# Motherboard.net
KiCad netlist of a schematic drawn in EAGLE
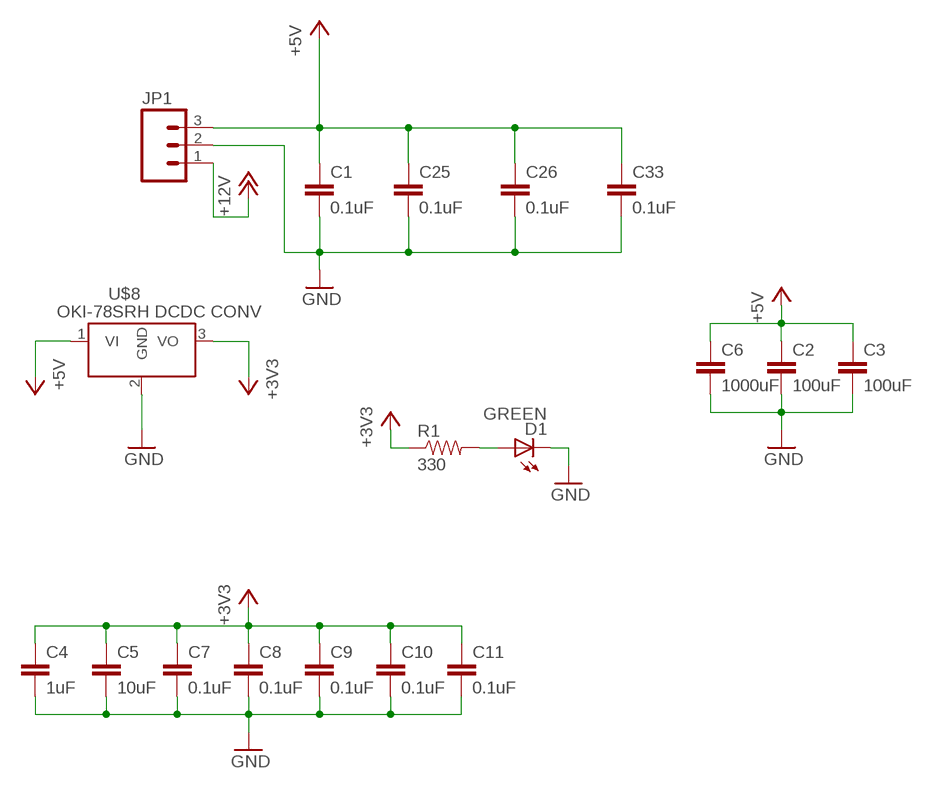
[diagram p0: schematic, sheet 1]
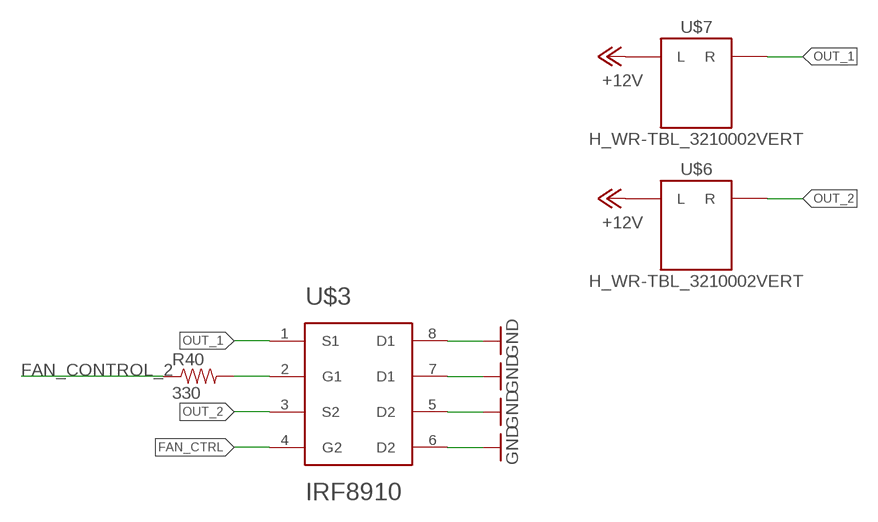
[diagram p1: schematic, sheet 2]
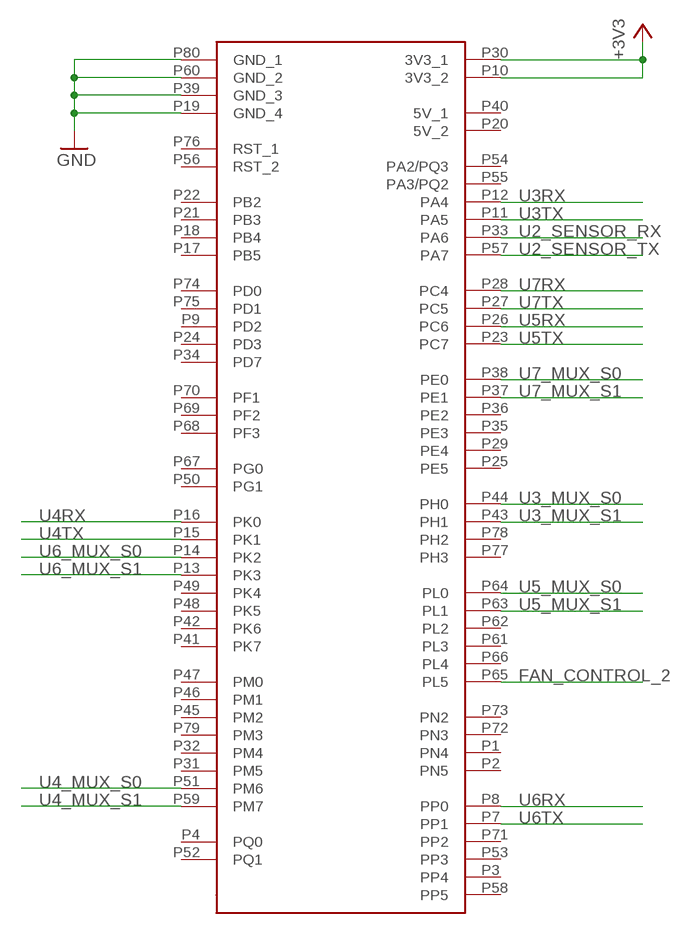
[diagram p2: schematic, sheet 3]
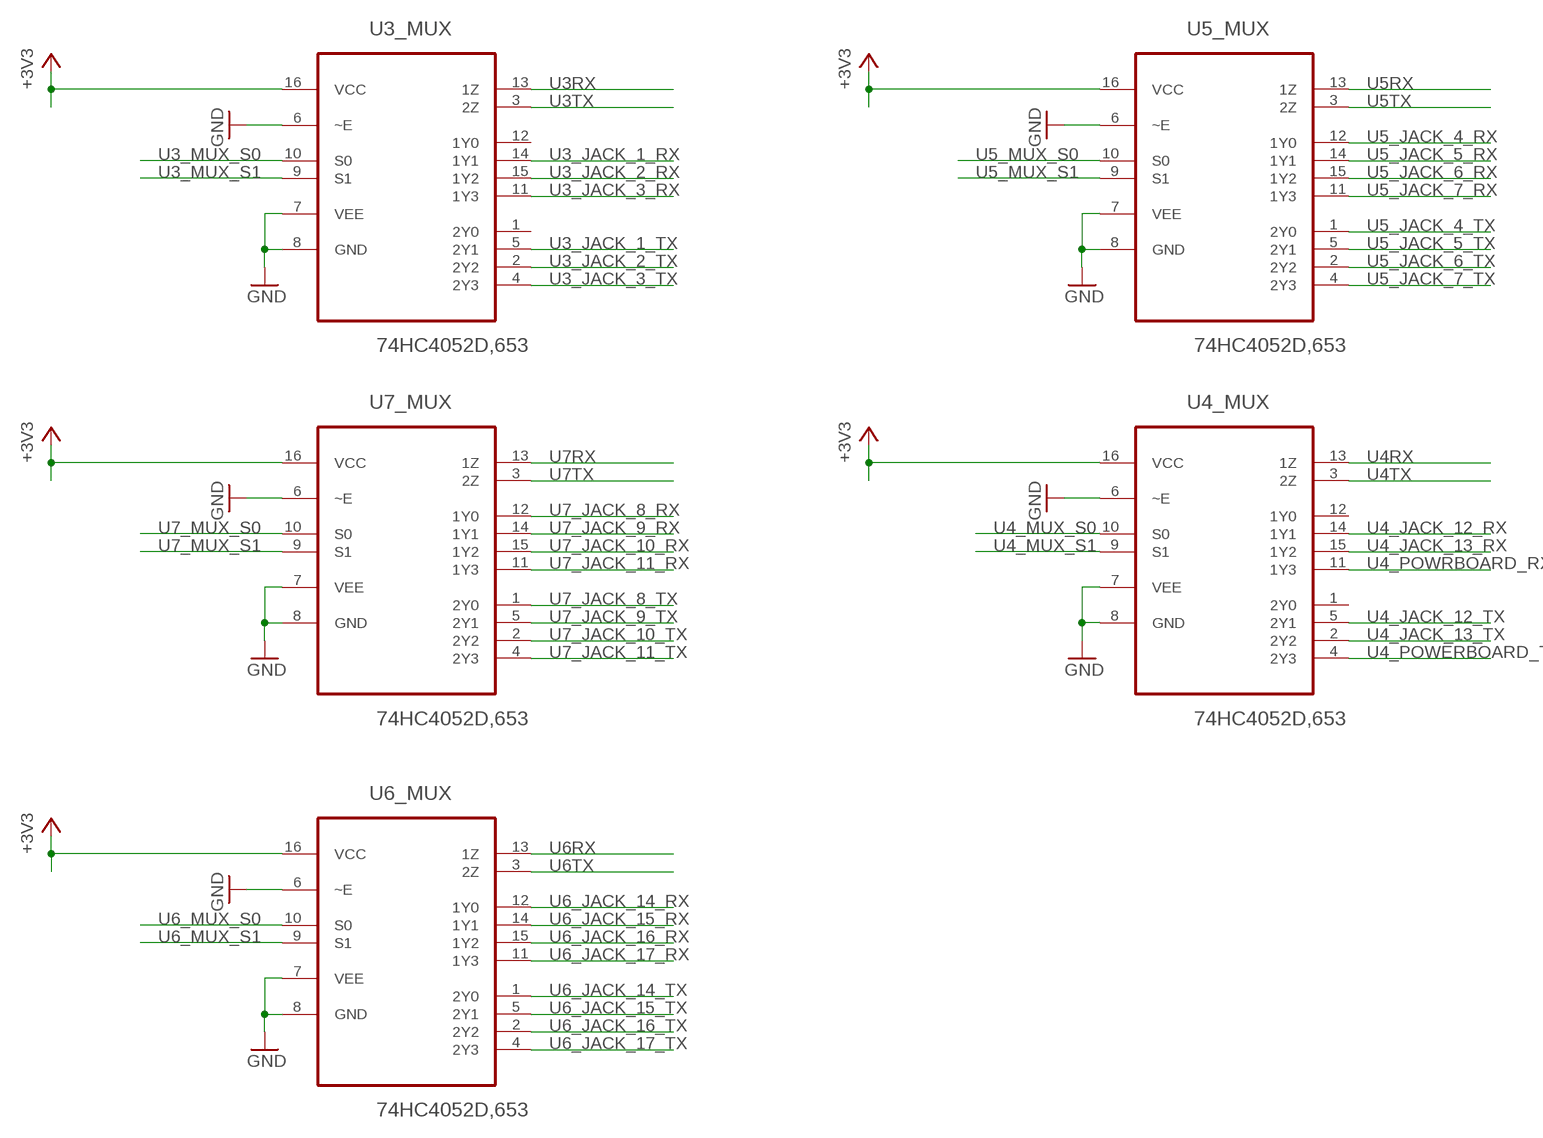
[diagram p3: schematic, sheet 4]
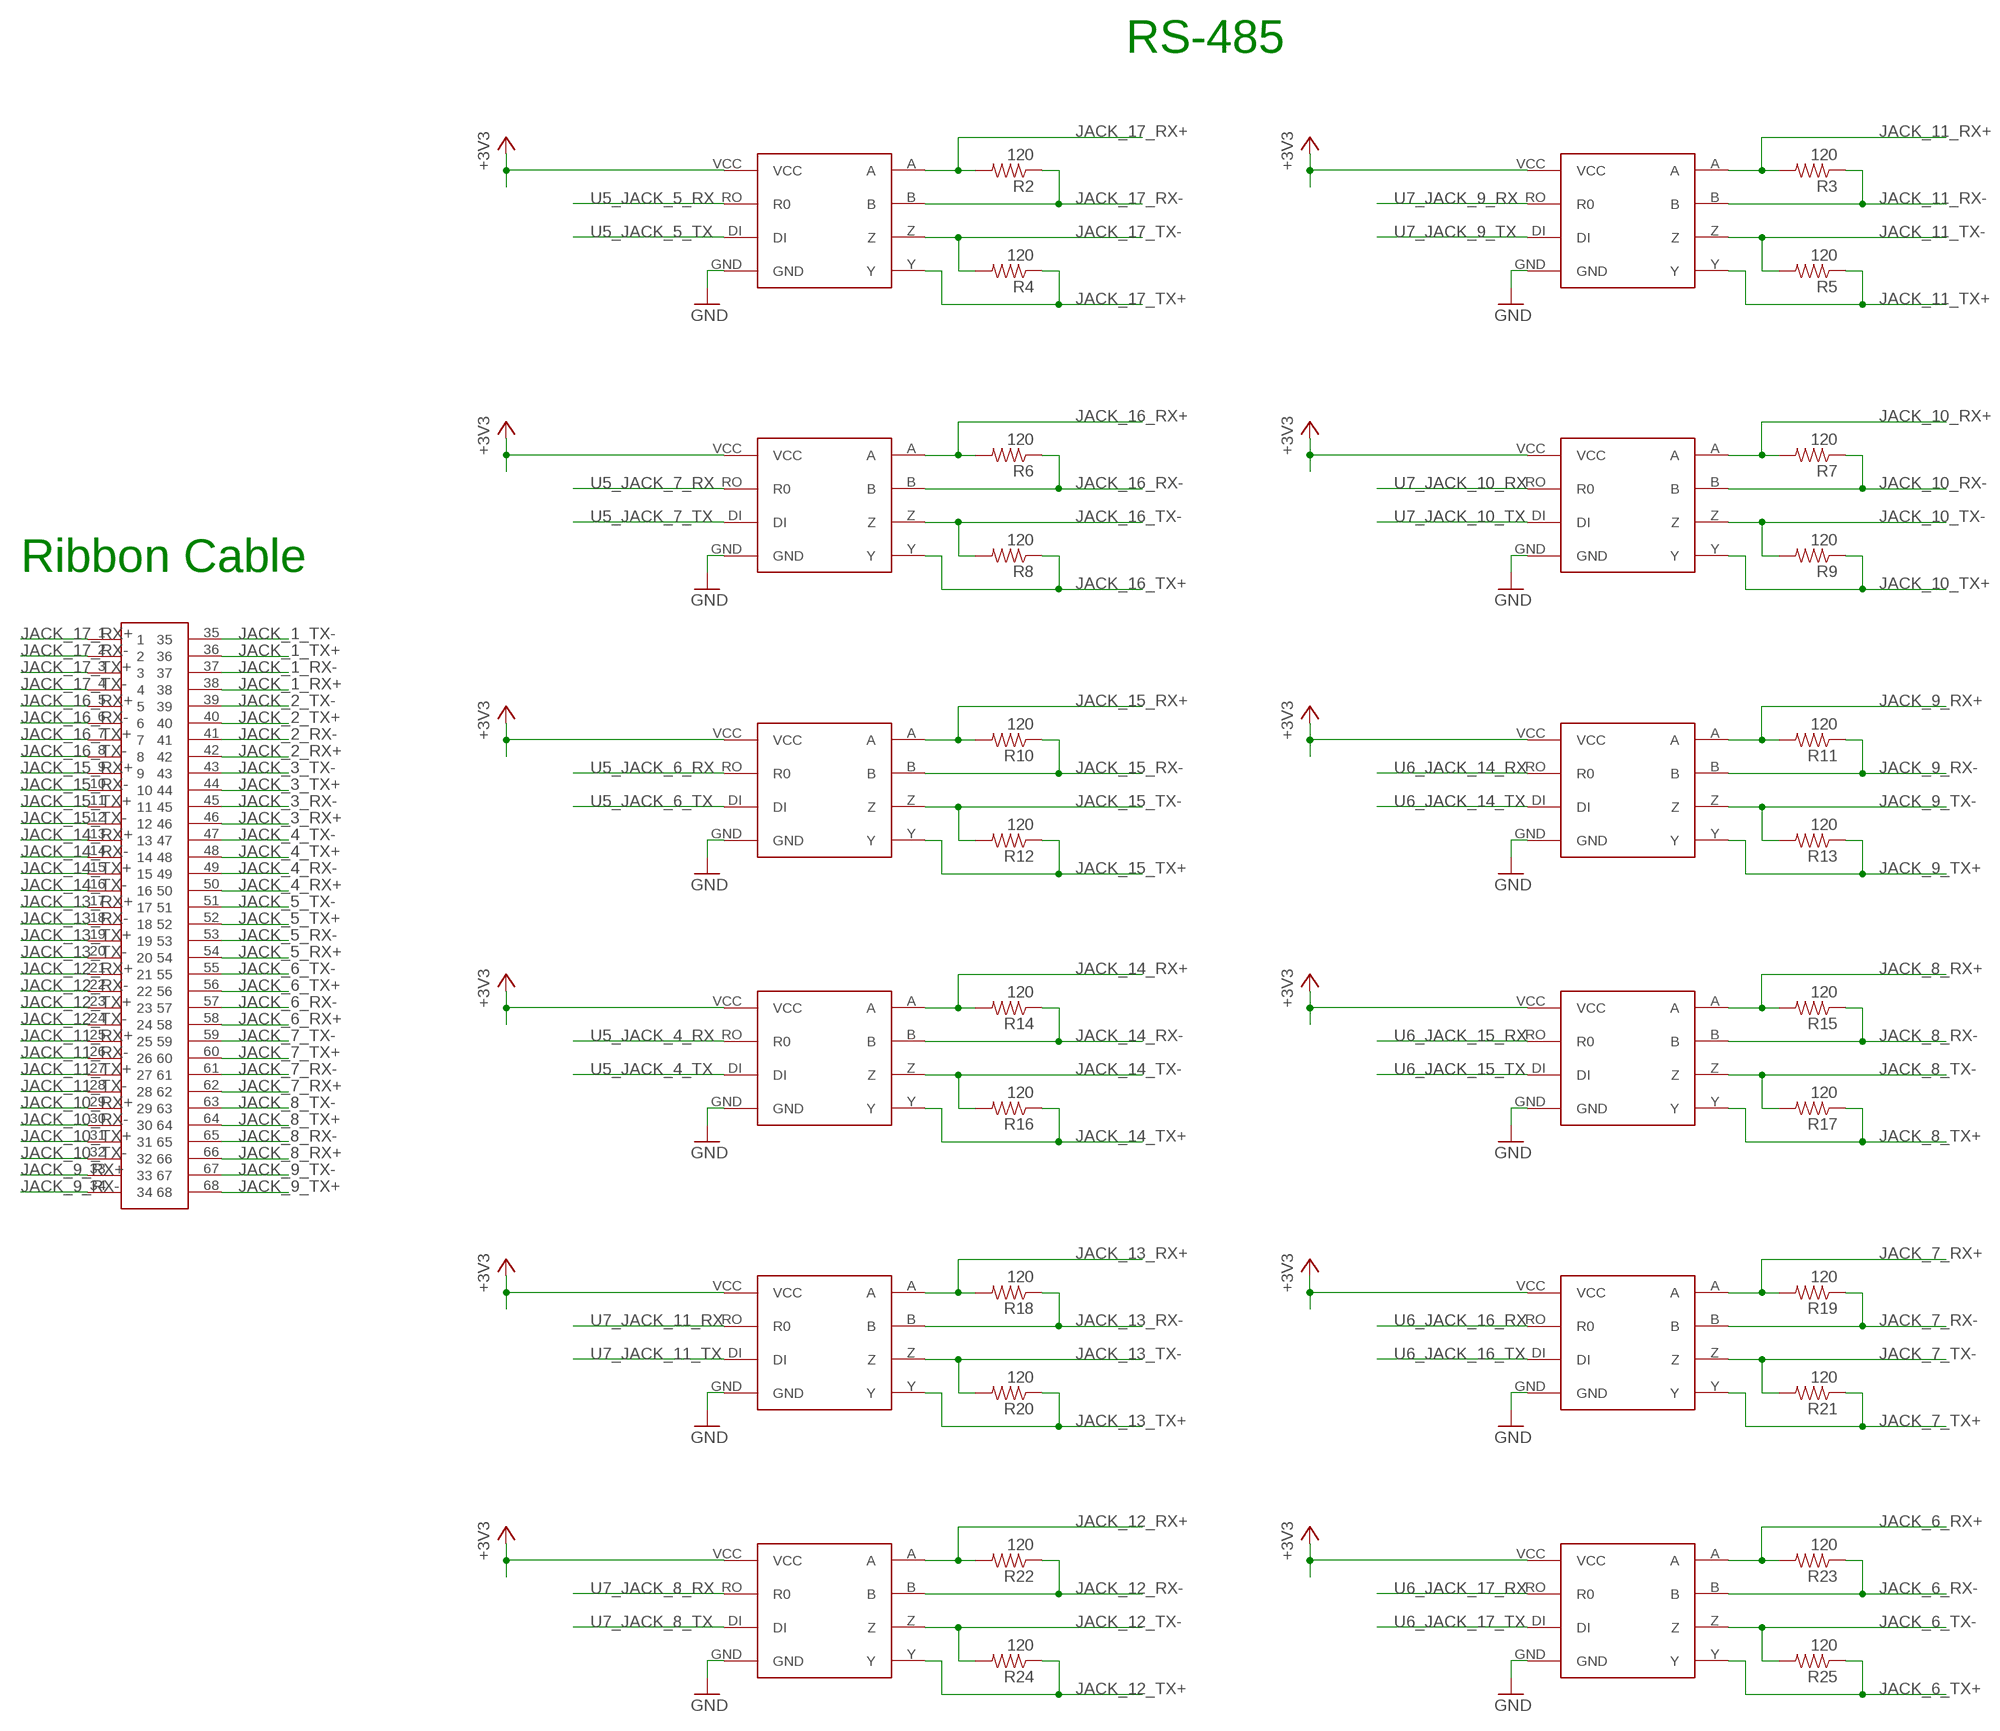
[diagram p4: schematic, sheet 5, part 1 of 2]
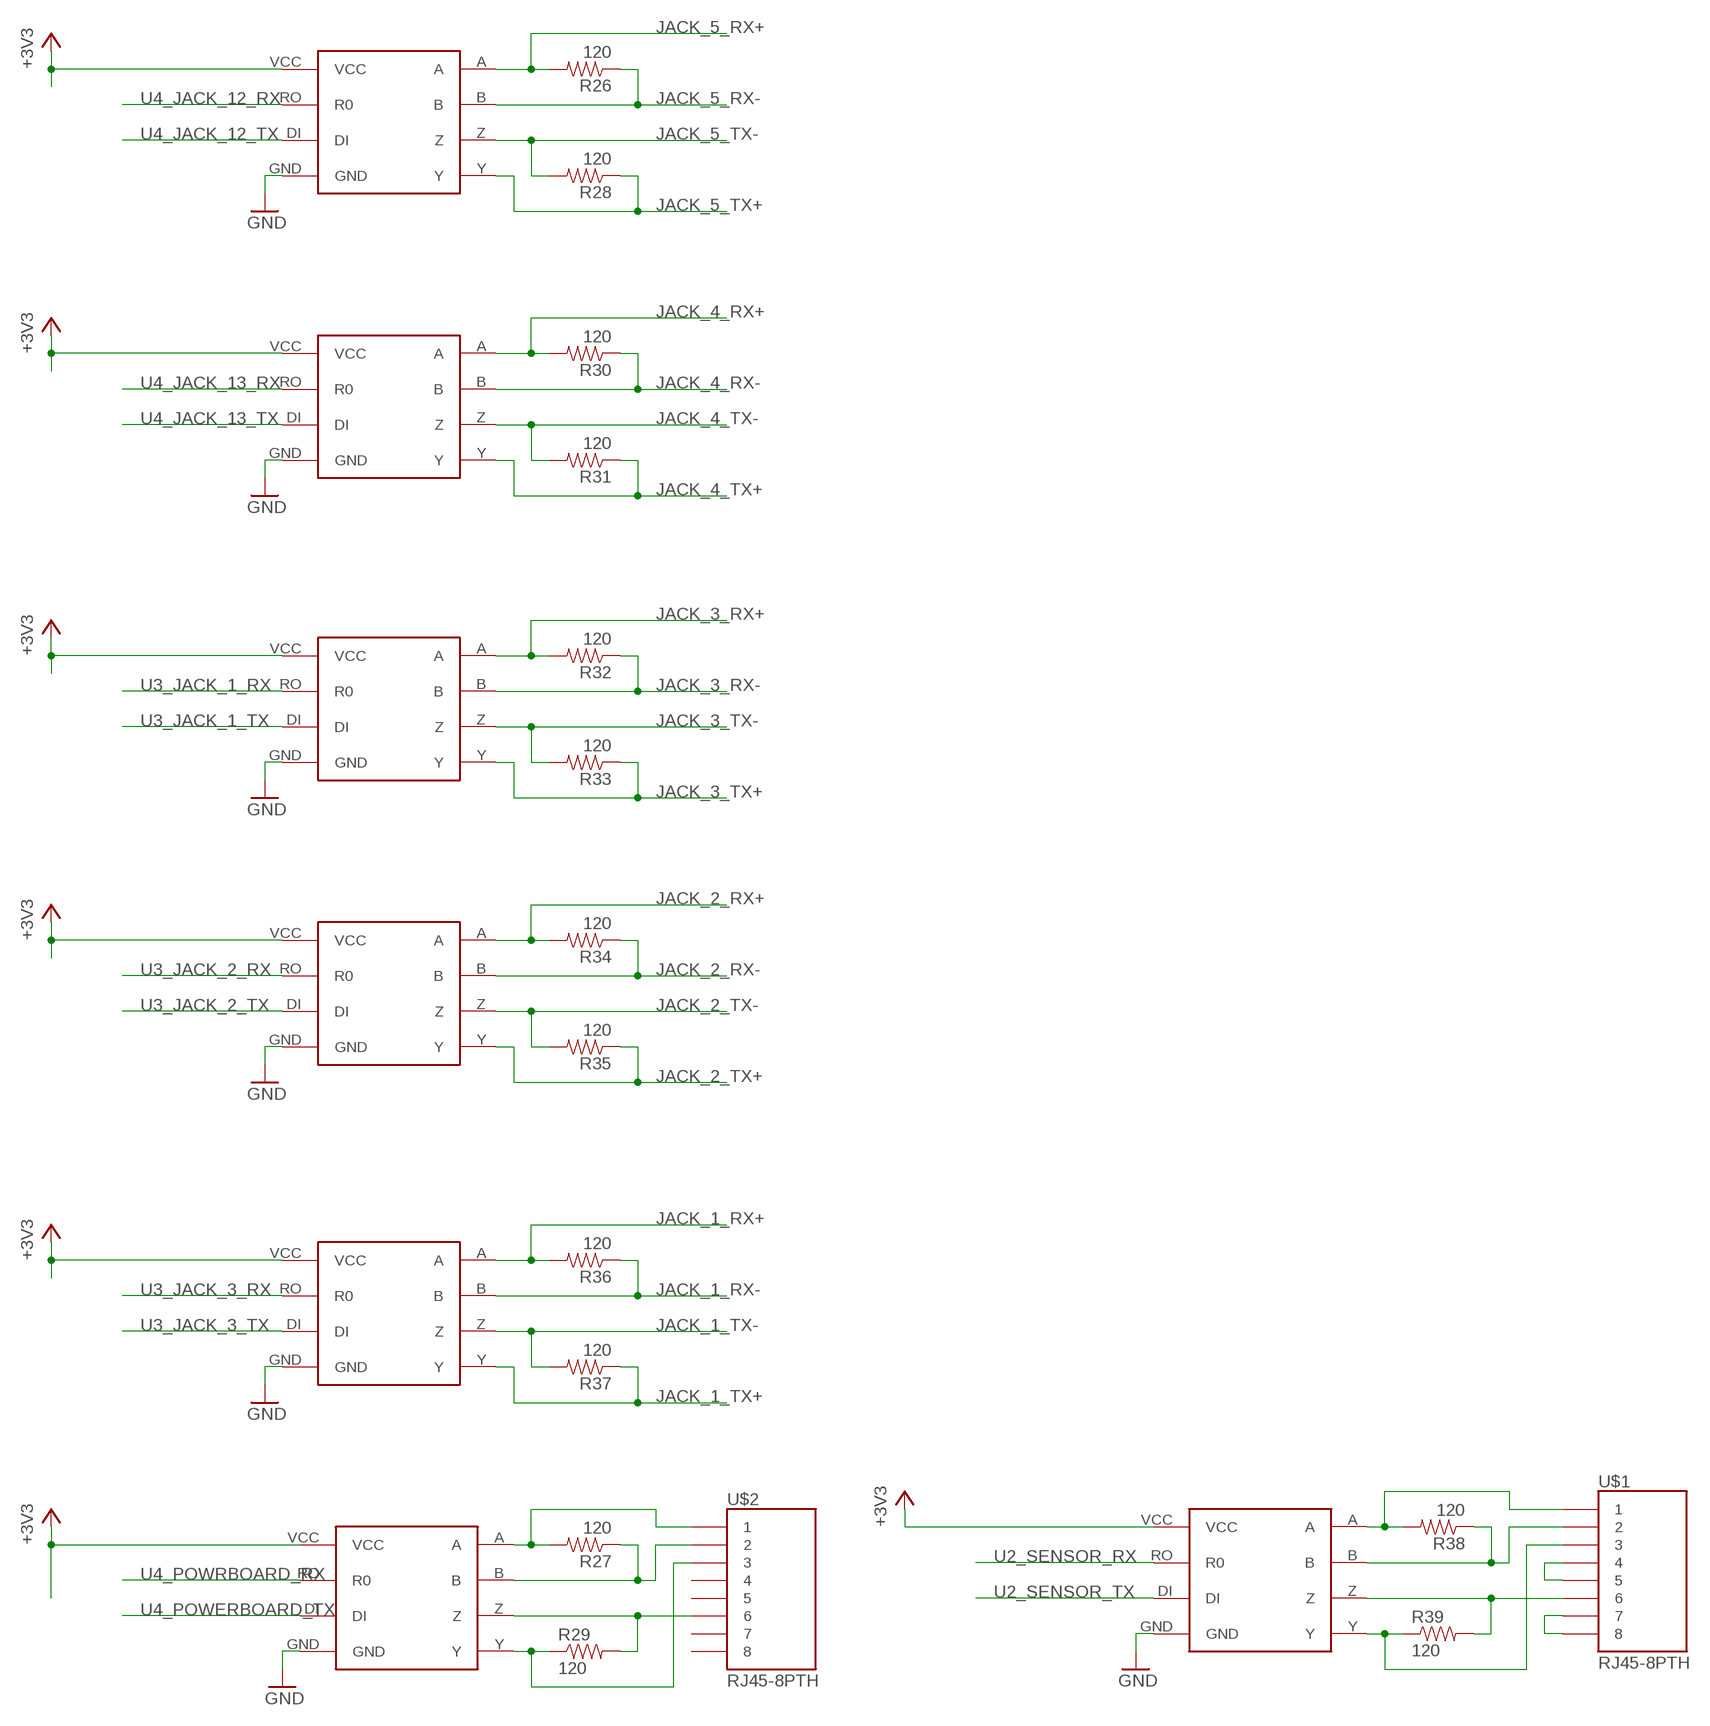
[diagram p5: schematic, sheet 5, part 2 of 2]
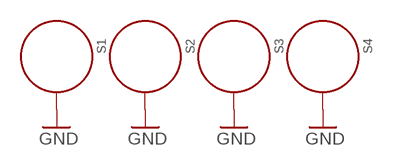
[diagram p6: schematic, sheet 6]

(export (version "E")
  (design (tool "Eeschema 10.0.6"))
  (components
    (comp (ref "S1")
      (value "STANDOFF_ELECTRICAL")
      (footprint "eagle-import:STANDOFF-ELECTRICAL")
      (libsource (lib "eagle-import") (part "STANDOFF_ELECTRICAL"))
    )
    (comp (ref "S2")
      (value "STANDOFF_ELECTRICAL")
      (footprint "eagle-import:STANDOFF-ELECTRICAL")
      (libsource (lib "eagle-import") (part "STANDOFF_ELECTRICAL"))
    )
    (comp (ref "S3")
      (value "STANDOFF_ELECTRICAL")
      (footprint "eagle-import:STANDOFF-ELECTRICAL")
      (libsource (lib "eagle-import") (part "STANDOFF_ELECTRICAL"))
    )
    (comp (ref "S4")
      (value "STANDOFF_ELECTRICAL")
      (footprint "eagle-import:STANDOFF-ELECTRICAL")
      (libsource (lib "eagle-import") (part "STANDOFF_ELECTRICAL"))
    )
    (comp (ref "R40")
      (value "330")
      (footprint "eagle-import:1206")
      (libsource (lib "eagle-import") (part "RESISTOR1206"))
    )
    (comp (ref "U$3")
      (value "IRF8910")
      (footprint "eagle-import:SO8")
      (libsource (lib "eagle-import") (part "IRF8910"))
    )
    (comp (ref "U$6")
      (value "H_WR-TBL_3210002VERT")
      (footprint "eagle-import:691321100002")
      (libsource (lib "eagle-import") (part "H_WR-TBL_3210002VERT"))
    )
    (comp (ref "U$7")
      (value "H_WR-TBL_3210002VERT")
      (footprint "eagle-import:691321100002")
      (libsource (lib "eagle-import") (part "H_WR-TBL_3210002VERT"))
    )
    (comp (ref "C1")
      (value "0.1uF")
      (footprint "eagle-import:1206")
      (libsource (lib "eagle-import") (part "CAP1206"))
    )
    (comp (ref "C2")
      (value "100uF")
      (footprint "eagle-import:1206")
      (libsource (lib "eagle-import") (part "CAP1206"))
    )
    (comp (ref "C3")
      (value "100uF")
      (footprint "eagle-import:1206")
      (libsource (lib "eagle-import") (part "CAP1206"))
    )
    (comp (ref "C4")
      (value "1uF")
      (footprint "eagle-import:1206")
      (libsource (lib "eagle-import") (part "CAP1206"))
    )
    (comp (ref "C5")
      (value "10uF")
      (footprint "eagle-import:1206")
      (libsource (lib "eagle-import") (part "CAP1206"))
    )
    (comp (ref "C6")
      (value "1000uF")
      (footprint "eagle-import:1206")
      (libsource (lib "eagle-import") (part "CAP1206"))
    )
    (comp (ref "C7")
      (value "0.1uF")
      (footprint "eagle-import:1206")
      (libsource (lib "eagle-import") (part "CAP1206"))
    )
    (comp (ref "C8")
      (value "0.1uF")
      (footprint "eagle-import:1206")
      (libsource (lib "eagle-import") (part "CAP1206"))
    )
    (comp (ref "C9")
      (value "0.1uF")
      (footprint "eagle-import:1206")
      (libsource (lib "eagle-import") (part "CAP1206"))
    )
    (comp (ref "C10")
      (value "0.1uF")
      (footprint "eagle-import:1206")
      (libsource (lib "eagle-import") (part "CAP1206"))
    )
    (comp (ref "C11")
      (value "0.1uF")
      (footprint "eagle-import:1206")
      (libsource (lib "eagle-import") (part "CAP1206"))
    )
    (comp (ref "C25")
      (value "0.1uF")
      (footprint "eagle-import:1206")
      (libsource (lib "eagle-import") (part "CAP1206"))
    )
    (comp (ref "C26")
      (value "0.1uF")
      (footprint "eagle-import:1206")
      (libsource (lib "eagle-import") (part "CAP1206"))
    )
    (comp (ref "C33")
      (value "0.1uF")
      (footprint "eagle-import:1206")
      (libsource (lib "eagle-import") (part "CAP1206"))
    )
    (comp (ref "D1")
      (value "GREEN")
      (footprint "eagle-import:LED-1206")
      (libsource (lib "eagle-import") (part "LED-GREENLARGE"))
    )
    (comp (ref "JP1")
      (value "M03SCREW")
      (footprint "eagle-import:SCREWTERMINAL-3.5MM-3")
      (libsource (lib "eagle-import") (part "M03SCREW"))
    )
    (comp (ref "R1")
      (value "330")
      (footprint "eagle-import:1206")
      (libsource (lib "eagle-import") (part "RESISTOR1206"))
    )
    (comp (ref "U$8")
      (value "Q_OKI-78SR")
      (footprint "eagle-import:OKI-78SRH")
      (libsource (lib "eagle-import") (part "Q_OKI-78SR"))
    )
    (comp (ref "U3_MUX")
      (value "74HC4052D,653")
      (footprint "eagle-import:SOIC127P600X175-16N")
      (libsource (lib "eagle-import") (part "74HC4052D,653"))
    )
    (comp (ref "U4_MUX")
      (value "74HC4052D,653")
      (footprint "eagle-import:SOIC127P600X175-16N")
      (libsource (lib "eagle-import") (part "74HC4052D,653"))
    )
    (comp (ref "U5_MUX")
      (value "74HC4052D,653")
      (footprint "eagle-import:SOIC127P600X175-16N")
      (libsource (lib "eagle-import") (part "74HC4052D,653"))
    )
    (comp (ref "U6_MUX")
      (value "74HC4052D,653")
      (footprint "eagle-import:SOIC127P600X175-16N")
      (libsource (lib "eagle-import") (part "74HC4052D,653"))
    )
    (comp (ref "U7_MUX")
      (value "74HC4052D,653")
      (footprint "eagle-import:SOIC127P600X175-16N")
      (libsource (lib "eagle-import") (part "74HC4052D,653"))
    )
    (comp (ref "R2")
      (value "120")
      (footprint "eagle-import:1206")
      (libsource (lib "eagle-import") (part "RESISTOR1206"))
    )
    (comp (ref "R3")
      (value "120")
      (footprint "eagle-import:1206")
      (libsource (lib "eagle-import") (part "RESISTOR1206"))
    )
    (comp (ref "R4")
      (value "120")
      (footprint "eagle-import:1206")
      (libsource (lib "eagle-import") (part "RESISTOR1206"))
    )
    (comp (ref "R5")
      (value "120")
      (footprint "eagle-import:1206")
      (libsource (lib "eagle-import") (part "RESISTOR1206"))
    )
    (comp (ref "R6")
      (value "120")
      (footprint "eagle-import:1206")
      (libsource (lib "eagle-import") (part "RESISTOR1206"))
    )
    (comp (ref "R7")
      (value "120")
      (footprint "eagle-import:1206")
      (libsource (lib "eagle-import") (part "RESISTOR1206"))
    )
    (comp (ref "R8")
      (value "120")
      (footprint "eagle-import:1206")
      (libsource (lib "eagle-import") (part "RESISTOR1206"))
    )
    (comp (ref "R9")
      (value "120")
      (footprint "eagle-import:1206")
      (libsource (lib "eagle-import") (part "RESISTOR1206"))
    )
    (comp (ref "R10")
      (value "120")
      (footprint "eagle-import:1206")
      (libsource (lib "eagle-import") (part "RESISTOR1206"))
    )
    (comp (ref "R11")
      (value "120")
      (footprint "eagle-import:1206")
      (libsource (lib "eagle-import") (part "RESISTOR1206"))
    )
    (comp (ref "R12")
      (value "120")
      (footprint "eagle-import:1206")
      (libsource (lib "eagle-import") (part "RESISTOR1206"))
    )
    (comp (ref "R13")
      (value "120")
      (footprint "eagle-import:1206")
      (libsource (lib "eagle-import") (part "RESISTOR1206"))
    )
    (comp (ref "R14")
      (value "120")
      (footprint "eagle-import:1206")
      (libsource (lib "eagle-import") (part "RESISTOR1206"))
    )
    (comp (ref "R15")
      (value "120")
      (footprint "eagle-import:1206")
      (libsource (lib "eagle-import") (part "RESISTOR1206"))
    )
    (comp (ref "R16")
      (value "120")
      (footprint "eagle-import:1206")
      (libsource (lib "eagle-import") (part "RESISTOR1206"))
    )
    (comp (ref "R17")
      (value "120")
      (footprint "eagle-import:1206")
      (libsource (lib "eagle-import") (part "RESISTOR1206"))
    )
    (comp (ref "R18")
      (value "120")
      (footprint "eagle-import:1206")
      (libsource (lib "eagle-import") (part "RESISTOR1206"))
    )
    (comp (ref "R19")
      (value "120")
      (footprint "eagle-import:1206")
      (libsource (lib "eagle-import") (part "RESISTOR1206"))
    )
    (comp (ref "R20")
      (value "120")
      (footprint "eagle-import:1206")
      (libsource (lib "eagle-import") (part "RESISTOR1206"))
    )
    (comp (ref "R21")
      (value "120")
      (footprint "eagle-import:1206")
      (libsource (lib "eagle-import") (part "RESISTOR1206"))
    )
    (comp (ref "R22")
      (value "120")
      (footprint "eagle-import:1206")
      (libsource (lib "eagle-import") (part "RESISTOR1206"))
    )
    (comp (ref "R23")
      (value "120")
      (footprint "eagle-import:1206")
      (libsource (lib "eagle-import") (part "RESISTOR1206"))
    )
    (comp (ref "R24")
      (value "120")
      (footprint "eagle-import:1206")
      (libsource (lib "eagle-import") (part "RESISTOR1206"))
    )
    (comp (ref "R25")
      (value "120")
      (footprint "eagle-import:1206")
      (libsource (lib "eagle-import") (part "RESISTOR1206"))
    )
    (comp (ref "R26")
      (value "120")
      (footprint "eagle-import:1206")
      (libsource (lib "eagle-import") (part "RESISTOR1206"))
    )
    (comp (ref "R27")
      (value "120")
      (footprint "eagle-import:1206")
      (libsource (lib "eagle-import") (part "RESISTOR1206"))
    )
    (comp (ref "R28")
      (value "120")
      (footprint "eagle-import:1206")
      (libsource (lib "eagle-import") (part "RESISTOR1206"))
    )
    (comp (ref "R29")
      (value "120")
      (footprint "eagle-import:1206")
      (libsource (lib "eagle-import") (part "RESISTOR1206"))
    )
    (comp (ref "R30")
      (value "120")
      (footprint "eagle-import:1206")
      (libsource (lib "eagle-import") (part "RESISTOR1206"))
    )
    (comp (ref "R31")
      (value "120")
      (footprint "eagle-import:1206")
      (libsource (lib "eagle-import") (part "RESISTOR1206"))
    )
    (comp (ref "R32")
      (value "120")
      (footprint "eagle-import:1206")
      (libsource (lib "eagle-import") (part "RESISTOR1206"))
    )
    (comp (ref "R33")
      (value "120")
      (footprint "eagle-import:1206")
      (libsource (lib "eagle-import") (part "RESISTOR1206"))
    )
    (comp (ref "R34")
      (value "120")
      (footprint "eagle-import:1206")
      (libsource (lib "eagle-import") (part "RESISTOR1206"))
    )
    (comp (ref "R35")
      (value "120")
      (footprint "eagle-import:1206")
      (libsource (lib "eagle-import") (part "RESISTOR1206"))
    )
    (comp (ref "R36")
      (value "120")
      (footprint "eagle-import:1206")
      (libsource (lib "eagle-import") (part "RESISTOR1206"))
    )
    (comp (ref "R37")
      (value "120")
      (footprint "eagle-import:1206")
      (libsource (lib "eagle-import") (part "RESISTOR1206"))
    )
    (comp (ref "R38")
      (value "120")
      (footprint "eagle-import:1206")
      (libsource (lib "eagle-import") (part "RESISTOR1206"))
    )
    (comp (ref "R39")
      (value "120")
      (footprint "eagle-import:1206")
      (libsource (lib "eagle-import") (part "RESISTOR1206"))
    )
    (comp (ref "RS-485-1")
      (value "MAX3077")
      (footprint "eagle-import:MAX3070E")
      (libsource (lib "eagle-import") (part "MAX3077"))
    )
    (comp (ref "RS-485-2")
      (value "MAX3077")
      (footprint "eagle-import:MAX3070E")
      (libsource (lib "eagle-import") (part "MAX3077"))
    )
    (comp (ref "RS_TRANS_1")
      (value "MAX3077")
      (footprint "eagle-import:MAX3070E")
      (libsource (lib "eagle-import") (part "MAX3077"))
    )
    (comp (ref "RS_TRANS_2")
      (value "MAX3077")
      (footprint "eagle-import:MAX3070E")
      (libsource (lib "eagle-import") (part "MAX3077"))
    )
    (comp (ref "RS_TRANS_3")
      (value "MAX3077")
      (footprint "eagle-import:MAX3070E")
      (libsource (lib "eagle-import") (part "MAX3077"))
    )
    (comp (ref "RS_TRANS_4")
      (value "MAX3077")
      (footprint "eagle-import:MAX3070E")
      (libsource (lib "eagle-import") (part "MAX3077"))
    )
    (comp (ref "RS_TRANS_5")
      (value "MAX3077")
      (footprint "eagle-import:MAX3070E")
      (libsource (lib "eagle-import") (part "MAX3077"))
    )
    (comp (ref "RS_TRANS_6")
      (value "MAX3077")
      (footprint "eagle-import:MAX3070E")
      (libsource (lib "eagle-import") (part "MAX3077"))
    )
    (comp (ref "RS_TRANS_7")
      (value "MAX3077")
      (footprint "eagle-import:MAX3070E")
      (libsource (lib "eagle-import") (part "MAX3077"))
    )
    (comp (ref "RS_TRANS_8")
      (value "MAX3077")
      (footprint "eagle-import:MAX3070E")
      (libsource (lib "eagle-import") (part "MAX3077"))
    )
    (comp (ref "RS_TRANS_9")
      (value "MAX3077")
      (footprint "eagle-import:MAX3070E")
      (libsource (lib "eagle-import") (part "MAX3077"))
    )
    (comp (ref "RS_TRANS_10")
      (value "MAX3077")
      (footprint "eagle-import:MAX3070E")
      (libsource (lib "eagle-import") (part "MAX3077"))
    )
    (comp (ref "RS_TRANS_11")
      (value "MAX3077")
      (footprint "eagle-import:MAX3070E")
      (libsource (lib "eagle-import") (part "MAX3077"))
    )
    (comp (ref "RS_TRANS_12")
      (value "MAX3077")
      (footprint "eagle-import:MAX3070E")
      (libsource (lib "eagle-import") (part "MAX3077"))
    )
    (comp (ref "RS_TRANS_13")
      (value "MAX3077")
      (footprint "eagle-import:MAX3070E")
      (libsource (lib "eagle-import") (part "MAX3077"))
    )
    (comp (ref "RS_TRANS_14")
      (value "MAX3077")
      (footprint "eagle-import:MAX3070E")
      (libsource (lib "eagle-import") (part "MAX3077"))
    )
    (comp (ref "RS_TRANS_15")
      (value "MAX3077")
      (footprint "eagle-import:MAX3070E")
      (libsource (lib "eagle-import") (part "MAX3077"))
    )
    (comp (ref "RS_TRANS_16")
      (value "MAX3077")
      (footprint "eagle-import:MAX3070E")
      (libsource (lib "eagle-import") (part "MAX3077"))
    )
    (comp (ref "RS_TRANS_17")
      (value "MAX3077")
      (footprint "eagle-import:MAX3070E")
      (libsource (lib "eagle-import") (part "MAX3077"))
    )
    (comp (ref "U$1")
      (value "RJ45-8PTH")
      (footprint "eagle-import:RJ45-8")
      (libsource (lib "eagle-import") (part "RJ45-8PTH"))
    )
    (comp (ref "U$2")
      (value "RJ45-8PTH")
      (footprint "eagle-import:RJ45-8")
      (libsource (lib "eagle-import") (part "RJ45-8PTH"))
    )
    (comp (ref "U$4")
      (value "TB60050685100")
      (footprint "eagle-import:60050685100")
      (libsource (lib "eagle-import") (part "TB60050685100"))
    )
    (comp (ref "U$5")
      (value "STELLARISLAUNCHPAD_CONNECTED")
      (footprint "eagle-import:STELLARISLAUNCHPAD_CONNECTED")
      (libsource (lib "eagle-import") (part "STELLARISLAUNCHPAD_CONNECTED"))
    )
  )
  (nets
    (net (code "1") (name "+3V3") (class "Default")
      (node (ref "C10") (pin "1") (pinfunction "1_1") (pintype "passive"))
      (node (ref "C11") (pin "1") (pinfunction "1_1") (pintype "passive"))
      (node (ref "C4") (pin "1") (pinfunction "1_1") (pintype "passive"))
      (node (ref "C5") (pin "1") (pinfunction "1_1") (pintype "passive"))
      (node (ref "C7") (pin "1") (pinfunction "1_1") (pintype "passive"))
      (node (ref "C8") (pin "1") (pinfunction "1_1") (pintype "passive"))
      (node (ref "C9") (pin "1") (pinfunction "1_1") (pintype "passive"))
      (node (ref "R1") (pin "1") (pinfunction "1_1") (pintype "passive"))
      (node (ref "RS-485-1") (pin "VCC") (pinfunction "VCC_VCC") (pintype "bidirectional"))
      (node (ref "RS-485-2") (pin "VCC") (pinfunction "VCC_VCC") (pintype "bidirectional"))
      (node (ref "RS_TRANS_1") (pin "VCC") (pinfunction "VCC_VCC") (pintype "bidirectional"))
      (node (ref "RS_TRANS_10") (pin "VCC") (pinfunction "VCC_VCC") (pintype "bidirectional"))
      (node (ref "RS_TRANS_11") (pin "VCC") (pinfunction "VCC_VCC") (pintype "bidirectional"))
      (node (ref "RS_TRANS_12") (pin "VCC") (pinfunction "VCC_VCC") (pintype "bidirectional"))
      (node (ref "RS_TRANS_13") (pin "VCC") (pinfunction "VCC_VCC") (pintype "bidirectional"))
      (node (ref "RS_TRANS_14") (pin "VCC") (pinfunction "VCC_VCC") (pintype "bidirectional"))
      (node (ref "RS_TRANS_15") (pin "VCC") (pinfunction "VCC_VCC") (pintype "bidirectional"))
      (node (ref "RS_TRANS_16") (pin "VCC") (pinfunction "VCC_VCC") (pintype "bidirectional"))
      (node (ref "RS_TRANS_17") (pin "VCC") (pinfunction "VCC_VCC") (pintype "bidirectional"))
      (node (ref "RS_TRANS_2") (pin "VCC") (pinfunction "VCC_VCC") (pintype "bidirectional"))
      (node (ref "RS_TRANS_3") (pin "VCC") (pinfunction "VCC_VCC") (pintype "bidirectional"))
      (node (ref "RS_TRANS_4") (pin "VCC") (pinfunction "VCC_VCC") (pintype "bidirectional"))
      (node (ref "RS_TRANS_5") (pin "VCC") (pinfunction "VCC_VCC") (pintype "bidirectional"))
      (node (ref "RS_TRANS_6") (pin "VCC") (pinfunction "VCC_VCC") (pintype "bidirectional"))
      (node (ref "RS_TRANS_7") (pin "VCC") (pinfunction "VCC_VCC") (pintype "bidirectional"))
      (node (ref "RS_TRANS_8") (pin "VCC") (pinfunction "VCC_VCC") (pintype "bidirectional"))
      (node (ref "RS_TRANS_9") (pin "VCC") (pinfunction "VCC_VCC") (pintype "bidirectional"))
      (node (ref "U$5") (pin "P10") (pinfunction "3V3_2_P10") (pintype "bidirectional"))
      (node (ref "U$5") (pin "P30") (pinfunction "3V3_1_P30") (pintype "bidirectional"))
      (node (ref "U$8") (pin "3") (pinfunction "VO_3") (pintype "bidirectional"))
      (node (ref "U3_MUX") (pin "16") (pinfunction "VCC_16") (pintype "power_in"))
      (node (ref "U4_MUX") (pin "16") (pinfunction "VCC_16") (pintype "power_in"))
      (node (ref "U5_MUX") (pin "16") (pinfunction "VCC_16") (pintype "power_in"))
      (node (ref "U6_MUX") (pin "16") (pinfunction "VCC_16") (pintype "power_in"))
      (node (ref "U7_MUX") (pin "16") (pinfunction "VCC_16") (pintype "power_in"))
    )
    (net (code "2") (name "+12V") (class "Default")
      (node (ref "JP1") (pin "1") (pinfunction "1_1") (pintype "passive"))
      (node (ref "U$6") (pin "L") (pinfunction "L_L") (pintype "bidirectional"))
      (node (ref "U$7") (pin "L") (pinfunction "L_L") (pintype "bidirectional"))
    )
    (net (code "3") (name "5V") (class "Default")
      (node (ref "C1") (pin "1") (pinfunction "1_1") (pintype "passive"))
      (node (ref "C2") (pin "1") (pinfunction "1_1") (pintype "passive"))
      (node (ref "C25") (pin "1") (pinfunction "1_1") (pintype "passive"))
      (node (ref "C26") (pin "1") (pinfunction "1_1") (pintype "passive"))
      (node (ref "C3") (pin "1") (pinfunction "1_1") (pintype "passive"))
      (node (ref "C33") (pin "1") (pinfunction "1_1") (pintype "passive"))
      (node (ref "C6") (pin "1") (pinfunction "1_1") (pintype "passive"))
      (node (ref "JP1") (pin "3") (pinfunction "3_3") (pintype "passive"))
      (node (ref "U$1") (pin "4") (pinfunction "4_4") (pintype "bidirectional"))
      (node (ref "U$1") (pin "5") (pinfunction "5_5") (pintype "bidirectional"))
      (node (ref "U$8") (pin "1") (pinfunction "VI_1") (pintype "bidirectional"))
    )
    (net (code "4") (name "FAN_CONTROL_2") (class "Default")
      (node (ref "R40") (pin "1") (pinfunction "1_1") (pintype "passive"))
      (node (ref "U$5") (pin "P65") (pinfunction "PL5_P65") (pintype "bidirectional"))
    )
    (net (code "5") (name "FAN_CTRL") (class "Default")
      (node (ref "R40") (pin "2") (pinfunction "2_2") (pintype "passive"))
      (node (ref "U$3") (pin "2") (pinfunction "G1_2") (pintype "bidirectional"))
      (node (ref "U$3") (pin "4") (pinfunction "G2_4") (pintype "bidirectional"))
    )
    (net (code "6") (name "GND") (class "Default")
      (node (ref "C1") (pin "2") (pinfunction "2_2") (pintype "passive"))
      (node (ref "C10") (pin "2") (pinfunction "2_2") (pintype "passive"))
      (node (ref "C11") (pin "2") (pinfunction "2_2") (pintype "passive"))
      (node (ref "C2") (pin "2") (pinfunction "2_2") (pintype "passive"))
      (node (ref "C25") (pin "2") (pinfunction "2_2") (pintype "passive"))
      (node (ref "C26") (pin "2") (pinfunction "2_2") (pintype "passive"))
      (node (ref "C3") (pin "2") (pinfunction "2_2") (pintype "passive"))
      (node (ref "C33") (pin "2") (pinfunction "2_2") (pintype "passive"))
      (node (ref "C4") (pin "2") (pinfunction "2_2") (pintype "passive"))
      (node (ref "C5") (pin "2") (pinfunction "2_2") (pintype "passive"))
      (node (ref "C6") (pin "2") (pinfunction "2_2") (pintype "passive"))
      (node (ref "C7") (pin "2") (pinfunction "2_2") (pintype "passive"))
      (node (ref "C8") (pin "2") (pinfunction "2_2") (pintype "passive"))
      (node (ref "C9") (pin "2") (pinfunction "2_2") (pintype "passive"))
      (node (ref "D1") (pin "C") (pinfunction "C_C") (pintype "passive"))
      (node (ref "JP1") (pin "2") (pinfunction "2_2") (pintype "passive"))
      (node (ref "RS-485-1") (pin "GND") (pinfunction "GND_GND") (pintype "bidirectional"))
      (node (ref "RS-485-2") (pin "GND") (pinfunction "GND_GND") (pintype "bidirectional"))
      (node (ref "RS_TRANS_1") (pin "GND") (pinfunction "GND_GND") (pintype "bidirectional"))
      (node (ref "RS_TRANS_10") (pin "GND") (pinfunction "GND_GND") (pintype "bidirectional"))
      (node (ref "RS_TRANS_11") (pin "GND") (pinfunction "GND_GND") (pintype "bidirectional"))
      (node (ref "RS_TRANS_12") (pin "GND") (pinfunction "GND_GND") (pintype "bidirectional"))
      (node (ref "RS_TRANS_13") (pin "GND") (pinfunction "GND_GND") (pintype "bidirectional"))
      (node (ref "RS_TRANS_14") (pin "GND") (pinfunction "GND_GND") (pintype "bidirectional"))
      (node (ref "RS_TRANS_15") (pin "GND") (pinfunction "GND_GND") (pintype "bidirectional"))
      (node (ref "RS_TRANS_16") (pin "GND") (pinfunction "GND_GND") (pintype "bidirectional"))
      (node (ref "RS_TRANS_17") (pin "GND") (pinfunction "GND_GND") (pintype "bidirectional"))
      (node (ref "RS_TRANS_2") (pin "GND") (pinfunction "GND_GND") (pintype "bidirectional"))
      (node (ref "RS_TRANS_3") (pin "GND") (pinfunction "GND_GND") (pintype "bidirectional"))
      (node (ref "RS_TRANS_4") (pin "GND") (pinfunction "GND_GND") (pintype "bidirectional"))
      (node (ref "RS_TRANS_5") (pin "GND") (pinfunction "GND_GND") (pintype "bidirectional"))
      (node (ref "RS_TRANS_6") (pin "GND") (pinfunction "GND_GND") (pintype "bidirectional"))
      (node (ref "RS_TRANS_7") (pin "GND") (pinfunction "GND_GND") (pintype "bidirectional"))
      (node (ref "RS_TRANS_8") (pin "GND") (pinfunction "GND_GND") (pintype "bidirectional"))
      (node (ref "RS_TRANS_9") (pin "GND") (pinfunction "GND_GND") (pintype "bidirectional"))
      (node (ref "S1") (pin "P1") (pinfunction "P$1_P1") (pintype "bidirectional"))
      (node (ref "S2") (pin "P1") (pinfunction "P$1_P1") (pintype "bidirectional"))
      (node (ref "S3") (pin "P1") (pinfunction "P$1_P1") (pintype "bidirectional"))
      (node (ref "S4") (pin "P1") (pinfunction "P$1_P1") (pintype "bidirectional"))
      (node (ref "U$1") (pin "7") (pinfunction "7_7") (pintype "bidirectional"))
      (node (ref "U$1") (pin "8") (pinfunction "8_8") (pintype "bidirectional"))
      (node (ref "U$3") (pin "5") (pinfunction "D2_5") (pintype "bidirectional"))
      (node (ref "U$3") (pin "6") (pinfunction "D2_6") (pintype "bidirectional"))
      (node (ref "U$3") (pin "7") (pinfunction "D1_7") (pintype "bidirectional"))
      (node (ref "U$3") (pin "8") (pinfunction "D1_8") (pintype "bidirectional"))
      (node (ref "U$5") (pin "P19") (pinfunction "GND_4_P19") (pintype "bidirectional"))
      (node (ref "U$5") (pin "P39") (pinfunction "GND_3_P39") (pintype "bidirectional"))
      (node (ref "U$5") (pin "P60") (pinfunction "GND_2_P60") (pintype "bidirectional"))
      (node (ref "U$5") (pin "P80") (pinfunction "GND_1_P80") (pintype "bidirectional"))
      (node (ref "U$8") (pin "2") (pinfunction "GND_2") (pintype "bidirectional"))
      (node (ref "U3_MUX") (pin "6") (pinfunction "~{E}_6") (pintype "input"))
      (node (ref "U3_MUX") (pin "7") (pinfunction "VEE_7") (pintype "power_in"))
      (node (ref "U3_MUX") (pin "8") (pinfunction "GND_8") (pintype "passive"))
      (node (ref "U4_MUX") (pin "6") (pinfunction "~{E}_6") (pintype "input"))
      (node (ref "U4_MUX") (pin "7") (pinfunction "VEE_7") (pintype "power_in"))
      (node (ref "U4_MUX") (pin "8") (pinfunction "GND_8") (pintype "passive"))
      (node (ref "U5_MUX") (pin "6") (pinfunction "~{E}_6") (pintype "input"))
      (node (ref "U5_MUX") (pin "7") (pinfunction "VEE_7") (pintype "power_in"))
      (node (ref "U5_MUX") (pin "8") (pinfunction "GND_8") (pintype "passive"))
      (node (ref "U6_MUX") (pin "6") (pinfunction "~{E}_6") (pintype "input"))
      (node (ref "U6_MUX") (pin "7") (pinfunction "VEE_7") (pintype "power_in"))
      (node (ref "U6_MUX") (pin "8") (pinfunction "GND_8") (pintype "passive"))
      (node (ref "U7_MUX") (pin "6") (pinfunction "~{E}_6") (pintype "input"))
      (node (ref "U7_MUX") (pin "7") (pinfunction "VEE_7") (pintype "power_in"))
      (node (ref "U7_MUX") (pin "8") (pinfunction "GND_8") (pintype "passive"))
    )
    (net (code "7") (name "JACK_1_RX+") (class "Default")
      (node (ref "R36") (pin "2") (pinfunction "2_2") (pintype "passive"))
      (node (ref "RS_TRANS_17") (pin "A") (pinfunction "A_A") (pintype "bidirectional"))
      (node (ref "U$4") (pin "38") (pinfunction "38_38") (pintype "bidirectional"))
    )
    (net (code "8") (name "JACK_1_RX-") (class "Default")
      (node (ref "R36") (pin "1") (pinfunction "1_1") (pintype "passive"))
      (node (ref "RS_TRANS_17") (pin "B") (pinfunction "B_B") (pintype "bidirectional"))
      (node (ref "U$4") (pin "37") (pinfunction "37_37") (pintype "bidirectional"))
    )
    (net (code "9") (name "JACK_1_TX+") (class "Default")
      (node (ref "R37") (pin "1") (pinfunction "1_1") (pintype "passive"))
      (node (ref "RS_TRANS_17") (pin "Y") (pinfunction "Y_Y") (pintype "bidirectional"))
      (node (ref "U$4") (pin "36") (pinfunction "36_36") (pintype "bidirectional"))
    )
    (net (code "10") (name "JACK_1_TX-") (class "Default")
      (node (ref "R37") (pin "2") (pinfunction "2_2") (pintype "passive"))
      (node (ref "RS_TRANS_17") (pin "Z") (pinfunction "Z_Z") (pintype "bidirectional"))
      (node (ref "U$4") (pin "35") (pinfunction "35_35") (pintype "bidirectional"))
    )
    (net (code "11") (name "JACK_2_RX+") (class "Default")
      (node (ref "R34") (pin "2") (pinfunction "2_2") (pintype "passive"))
      (node (ref "RS_TRANS_16") (pin "A") (pinfunction "A_A") (pintype "bidirectional"))
      (node (ref "U$4") (pin "42") (pinfunction "42_42") (pintype "bidirectional"))
    )
    (net (code "12") (name "JACK_2_RX-") (class "Default")
      (node (ref "R34") (pin "1") (pinfunction "1_1") (pintype "passive"))
      (node (ref "RS_TRANS_16") (pin "B") (pinfunction "B_B") (pintype "bidirectional"))
      (node (ref "U$4") (pin "41") (pinfunction "41_41") (pintype "bidirectional"))
    )
    (net (code "13") (name "JACK_2_TX+") (class "Default")
      (node (ref "R35") (pin "1") (pinfunction "1_1") (pintype "passive"))
      (node (ref "RS_TRANS_16") (pin "Y") (pinfunction "Y_Y") (pintype "bidirectional"))
      (node (ref "U$4") (pin "40") (pinfunction "40_40") (pintype "bidirectional"))
    )
    (net (code "14") (name "JACK_2_TX-") (class "Default")
      (node (ref "R35") (pin "2") (pinfunction "2_2") (pintype "passive"))
      (node (ref "RS_TRANS_16") (pin "Z") (pinfunction "Z_Z") (pintype "bidirectional"))
      (node (ref "U$4") (pin "39") (pinfunction "39_39") (pintype "bidirectional"))
    )
    (net (code "15") (name "JACK_3_RX+") (class "Default")
      (node (ref "R32") (pin "2") (pinfunction "2_2") (pintype "passive"))
      (node (ref "RS_TRANS_15") (pin "A") (pinfunction "A_A") (pintype "bidirectional"))
      (node (ref "U$4") (pin "46") (pinfunction "46_46") (pintype "bidirectional"))
    )
    (net (code "16") (name "JACK_3_RX-") (class "Default")
      (node (ref "R32") (pin "1") (pinfunction "1_1") (pintype "passive"))
      (node (ref "RS_TRANS_15") (pin "B") (pinfunction "B_B") (pintype "bidirectional"))
      (node (ref "U$4") (pin "45") (pinfunction "45_45") (pintype "bidirectional"))
    )
    (net (code "17") (name "JACK_3_TX+") (class "Default")
      (node (ref "R33") (pin "1") (pinfunction "1_1") (pintype "passive"))
      (node (ref "RS_TRANS_15") (pin "Y") (pinfunction "Y_Y") (pintype "bidirectional"))
      (node (ref "U$4") (pin "44") (pinfunction "44_44") (pintype "bidirectional"))
    )
    (net (code "18") (name "JACK_3_TX-") (class "Default")
      (node (ref "R33") (pin "2") (pinfunction "2_2") (pintype "passive"))
      (node (ref "RS_TRANS_15") (pin "Z") (pinfunction "Z_Z") (pintype "bidirectional"))
      (node (ref "U$4") (pin "43") (pinfunction "43_43") (pintype "bidirectional"))
    )
    (net (code "19") (name "JACK_4_RX+") (class "Default")
      (node (ref "R30") (pin "2") (pinfunction "2_2") (pintype "passive"))
      (node (ref "RS_TRANS_14") (pin "A") (pinfunction "A_A") (pintype "bidirectional"))
      (node (ref "U$4") (pin "50") (pinfunction "50_50") (pintype "bidirectional"))
    )
    (net (code "20") (name "JACK_4_RX-") (class "Default")
      (node (ref "R30") (pin "1") (pinfunction "1_1") (pintype "passive"))
      (node (ref "RS_TRANS_14") (pin "B") (pinfunction "B_B") (pintype "bidirectional"))
      (node (ref "U$4") (pin "49") (pinfunction "49_49") (pintype "bidirectional"))
    )
    (net (code "21") (name "JACK_4_TX+") (class "Default")
      (node (ref "R31") (pin "1") (pinfunction "1_1") (pintype "passive"))
      (node (ref "RS_TRANS_14") (pin "Y") (pinfunction "Y_Y") (pintype "bidirectional"))
      (node (ref "U$4") (pin "48") (pinfunction "48_48") (pintype "bidirectional"))
    )
    (net (code "22") (name "JACK_4_TX-") (class "Default")
      (node (ref "R31") (pin "2") (pinfunction "2_2") (pintype "passive"))
      (node (ref "RS_TRANS_14") (pin "Z") (pinfunction "Z_Z") (pintype "bidirectional"))
      (node (ref "U$4") (pin "47") (pinfunction "47_47") (pintype "bidirectional"))
    )
    (net (code "23") (name "JACK_5_RX+") (class "Default")
      (node (ref "R26") (pin "2") (pinfunction "2_2") (pintype "passive"))
      (node (ref "RS_TRANS_13") (pin "A") (pinfunction "A_A") (pintype "bidirectional"))
      (node (ref "U$4") (pin "54") (pinfunction "54_54") (pintype "bidirectional"))
    )
    (net (code "24") (name "JACK_5_RX-") (class "Default")
      (node (ref "R26") (pin "1") (pinfunction "1_1") (pintype "passive"))
      (node (ref "RS_TRANS_13") (pin "B") (pinfunction "B_B") (pintype "bidirectional"))
      (node (ref "U$4") (pin "53") (pinfunction "53_53") (pintype "bidirectional"))
    )
    (net (code "25") (name "JACK_5_TX+") (class "Default")
      (node (ref "R28") (pin "1") (pinfunction "1_1") (pintype "passive"))
      (node (ref "RS_TRANS_13") (pin "Y") (pinfunction "Y_Y") (pintype "bidirectional"))
      (node (ref "U$4") (pin "52") (pinfunction "52_52") (pintype "bidirectional"))
    )
    (net (code "26") (name "JACK_5_TX-") (class "Default")
      (node (ref "R28") (pin "2") (pinfunction "2_2") (pintype "passive"))
      (node (ref "RS_TRANS_13") (pin "Z") (pinfunction "Z_Z") (pintype "bidirectional"))
      (node (ref "U$4") (pin "51") (pinfunction "51_51") (pintype "bidirectional"))
    )
    (net (code "27") (name "JACK_6_RX+") (class "Default")
      (node (ref "R23") (pin "2") (pinfunction "2_2") (pintype "passive"))
      (node (ref "RS_TRANS_12") (pin "A") (pinfunction "A_A") (pintype "bidirectional"))
      (node (ref "U$4") (pin "58") (pinfunction "58_58") (pintype "bidirectional"))
    )
    (net (code "28") (name "JACK_6_RX-") (class "Default")
      (node (ref "R23") (pin "1") (pinfunction "1_1") (pintype "passive"))
      (node (ref "RS_TRANS_12") (pin "B") (pinfunction "B_B") (pintype "bidirectional"))
      (node (ref "U$4") (pin "57") (pinfunction "57_57") (pintype "bidirectional"))
    )
    (net (code "29") (name "JACK_6_TX+") (class "Default")
      (node (ref "R25") (pin "1") (pinfunction "1_1") (pintype "passive"))
      (node (ref "RS_TRANS_12") (pin "Y") (pinfunction "Y_Y") (pintype "bidirectional"))
      (node (ref "U$4") (pin "56") (pinfunction "56_56") (pintype "bidirectional"))
    )
    (net (code "30") (name "JACK_6_TX-") (class "Default")
      (node (ref "R25") (pin "2") (pinfunction "2_2") (pintype "passive"))
      (node (ref "RS_TRANS_12") (pin "Z") (pinfunction "Z_Z") (pintype "bidirectional"))
      (node (ref "U$4") (pin "55") (pinfunction "55_55") (pintype "bidirectional"))
    )
    (net (code "31") (name "JACK_7_RX+") (class "Default")
      (node (ref "R19") (pin "2") (pinfunction "2_2") (pintype "passive"))
      (node (ref "RS_TRANS_10") (pin "A") (pinfunction "A_A") (pintype "bidirectional"))
      (node (ref "U$4") (pin "62") (pinfunction "62_62") (pintype "bidirectional"))
    )
    (net (code "32") (name "JACK_7_RX-") (class "Default")
      (node (ref "R19") (pin "1") (pinfunction "1_1") (pintype "passive"))
      (node (ref "RS_TRANS_10") (pin "B") (pinfunction "B_B") (pintype "bidirectional"))
      (node (ref "U$4") (pin "61") (pinfunction "61_61") (pintype "bidirectional"))
    )
    (net (code "33") (name "JACK_7_TX+") (class "Default")
      (node (ref "R21") (pin "1") (pinfunction "1_1") (pintype "passive"))
      (node (ref "RS_TRANS_10") (pin "Y") (pinfunction "Y_Y") (pintype "bidirectional"))
      (node (ref "U$4") (pin "60") (pinfunction "60_60") (pintype "bidirectional"))
    )
    (net (code "34") (name "JACK_7_TX-") (class "Default")
      (node (ref "R21") (pin "2") (pinfunction "2_2") (pintype "passive"))
      (node (ref "RS_TRANS_10") (pin "Z") (pinfunction "Z_Z") (pintype "bidirectional"))
      (node (ref "U$4") (pin "59") (pinfunction "59_59") (pintype "bidirectional"))
    )
    (net (code "35") (name "JACK_8_RX+") (class "Default")
      (node (ref "R15") (pin "2") (pinfunction "2_2") (pintype "passive"))
      (node (ref "RS_TRANS_8") (pin "A") (pinfunction "A_A") (pintype "bidirectional"))
      (node (ref "U$4") (pin "66") (pinfunction "66_66") (pintype "bidirectional"))
    )
    (net (code "36") (name "JACK_8_RX-") (class "Default")
      (node (ref "R15") (pin "1") (pinfunction "1_1") (pintype "passive"))
      (node (ref "RS_TRANS_8") (pin "B") (pinfunction "B_B") (pintype "bidirectional"))
      (node (ref "U$4") (pin "65") (pinfunction "65_65") (pintype "bidirectional"))
    )
    (net (code "37") (name "JACK_8_TX+") (class "Default")
      (node (ref "R17") (pin "1") (pinfunction "1_1") (pintype "passive"))
      (node (ref "RS_TRANS_8") (pin "Y") (pinfunction "Y_Y") (pintype "bidirectional"))
      (node (ref "U$4") (pin "64") (pinfunction "64_64") (pintype "bidirectional"))
    )
    (net (code "38") (name "JACK_8_TX-") (class "Default")
      (node (ref "R17") (pin "2") (pinfunction "2_2") (pintype "passive"))
      (node (ref "RS_TRANS_8") (pin "Z") (pinfunction "Z_Z") (pintype "bidirectional"))
      (node (ref "U$4") (pin "63") (pinfunction "63_63") (pintype "bidirectional"))
    )
    (net (code "39") (name "JACK_9_RX+") (class "Default")
      (node (ref "R11") (pin "2") (pinfunction "2_2") (pintype "passive"))
      (node (ref "RS_TRANS_6") (pin "A") (pinfunction "A_A") (pintype "bidirectional"))
      (node (ref "U$4") (pin "33") (pinfunction "33_33") (pintype "bidirectional"))
    )
    (net (code "40") (name "JACK_9_RX-") (class "Default")
      (node (ref "R11") (pin "1") (pinfunction "1_1") (pintype "passive"))
      (node (ref "RS_TRANS_6") (pin "B") (pinfunction "B_B") (pintype "bidirectional"))
      (node (ref "U$4") (pin "34") (pinfunction "34_34") (pintype "bidirectional"))
    )
    (net (code "41") (name "JACK_9_TX+") (class "Default")
      (node (ref "R13") (pin "1") (pinfunction "1_1") (pintype "passive"))
      (node (ref "RS_TRANS_6") (pin "Y") (pinfunction "Y_Y") (pintype "bidirectional"))
      (node (ref "U$4") (pin "68") (pinfunction "68_68") (pintype "bidirectional"))
    )
    (net (code "42") (name "JACK_9_TX-") (class "Default")
      (node (ref "R13") (pin "2") (pinfunction "2_2") (pintype "passive"))
      (node (ref "RS_TRANS_6") (pin "Z") (pinfunction "Z_Z") (pintype "bidirectional"))
      (node (ref "U$4") (pin "67") (pinfunction "67_67") (pintype "bidirectional"))
    )
    (net (code "43") (name "JACK_10_RX+") (class "Default")
      (node (ref "R7") (pin "2") (pinfunction "2_2") (pintype "passive"))
      (node (ref "RS_TRANS_4") (pin "A") (pinfunction "A_A") (pintype "bidirectional"))
      (node (ref "U$4") (pin "29") (pinfunction "29_29") (pintype "bidirectional"))
    )
    (net (code "44") (name "JACK_10_RX-") (class "Default")
      (node (ref "R7") (pin "1") (pinfunction "1_1") (pintype "passive"))
      (node (ref "RS_TRANS_4") (pin "B") (pinfunction "B_B") (pintype "bidirectional"))
      (node (ref "U$4") (pin "30") (pinfunction "30_30") (pintype "bidirectional"))
    )
    (net (code "45") (name "JACK_10_TX+") (class "Default")
      (node (ref "R9") (pin "1") (pinfunction "1_1") (pintype "passive"))
      (node (ref "RS_TRANS_4") (pin "Y") (pinfunction "Y_Y") (pintype "bidirectional"))
      (node (ref "U$4") (pin "31") (pinfunction "31_31") (pintype "bidirectional"))
    )
    (net (code "46") (name "JACK_10_TX-") (class "Default")
      (node (ref "R9") (pin "2") (pinfunction "2_2") (pintype "passive"))
      (node (ref "RS_TRANS_4") (pin "Z") (pinfunction "Z_Z") (pintype "bidirectional"))
      (node (ref "U$4") (pin "32") (pinfunction "32_32") (pintype "bidirectional"))
    )
    (net (code "47") (name "JACK_11_RX+") (class "Default")
      (node (ref "R3") (pin "2") (pinfunction "2_2") (pintype "passive"))
      (node (ref "RS_TRANS_2") (pin "A") (pinfunction "A_A") (pintype "bidirectional"))
      (node (ref "U$4") (pin "25") (pinfunction "25_25") (pintype "bidirectional"))
    )
    (net (code "48") (name "JACK_11_RX-") (class "Default")
      (node (ref "R3") (pin "1") (pinfunction "1_1") (pintype "passive"))
      (node (ref "RS_TRANS_2") (pin "B") (pinfunction "B_B") (pintype "bidirectional"))
      (node (ref "U$4") (pin "26") (pinfunction "26_26") (pintype "bidirectional"))
    )
    (net (code "49") (name "JACK_11_TX+") (class "Default")
      (node (ref "R5") (pin "1") (pinfunction "1_1") (pintype "passive"))
      (node (ref "RS_TRANS_2") (pin "Y") (pinfunction "Y_Y") (pintype "bidirectional"))
      (node (ref "U$4") (pin "27") (pinfunction "27_27") (pintype "bidirectional"))
    )
    (net (code "50") (name "JACK_11_TX-") (class "Default")
      (node (ref "R5") (pin "2") (pinfunction "2_2") (pintype "passive"))
      (node (ref "RS_TRANS_2") (pin "Z") (pinfunction "Z_Z") (pintype "bidirectional"))
      (node (ref "U$4") (pin "28") (pinfunction "28_28") (pintype "bidirectional"))
    )
    (net (code "51") (name "JACK_12_RX+") (class "Default")
      (node (ref "R22") (pin "2") (pinfunction "2_2") (pintype "passive"))
      (node (ref "RS_TRANS_11") (pin "A") (pinfunction "A_A") (pintype "bidirectional"))
      (node (ref "U$4") (pin "21") (pinfunction "21_21") (pintype "bidirectional"))
    )
    (net (code "52") (name "JACK_12_RX-") (class "Default")
      (node (ref "R22") (pin "1") (pinfunction "1_1") (pintype "passive"))
      (node (ref "RS_TRANS_11") (pin "B") (pinfunction "B_B") (pintype "bidirectional"))
      (node (ref "U$4") (pin "22") (pinfunction "22_22") (pintype "bidirectional"))
    )
    (net (code "53") (name "JACK_12_TX+") (class "Default")
      (node (ref "R24") (pin "1") (pinfunction "1_1") (pintype "passive"))
      (node (ref "RS_TRANS_11") (pin "Y") (pinfunction "Y_Y") (pintype "bidirectional"))
      (node (ref "U$4") (pin "23") (pinfunction "23_23") (pintype "bidirectional"))
    )
    (net (code "54") (name "JACK_12_TX-") (class "Default")
      (node (ref "R24") (pin "2") (pinfunction "2_2") (pintype "passive"))
      (node (ref "RS_TRANS_11") (pin "Z") (pinfunction "Z_Z") (pintype "bidirectional"))
      (node (ref "U$4") (pin "24") (pinfunction "24_24") (pintype "bidirectional"))
    )
    (net (code "55") (name "JACK_13_RX+") (class "Default")
      (node (ref "R18") (pin "2") (pinfunction "2_2") (pintype "passive"))
      (node (ref "RS_TRANS_9") (pin "A") (pinfunction "A_A") (pintype "bidirectional"))
      (node (ref "U$4") (pin "17") (pinfunction "17_17") (pintype "bidirectional"))
    )
    (net (code "56") (name "JACK_13_RX-") (class "Default")
      (node (ref "R18") (pin "1") (pinfunction "1_1") (pintype "passive"))
      (node (ref "RS_TRANS_9") (pin "B") (pinfunction "B_B") (pintype "bidirectional"))
      (node (ref "U$4") (pin "18") (pinfunction "18_18") (pintype "bidirectional"))
    )
    (net (code "57") (name "JACK_13_TX+") (class "Default")
      (node (ref "R20") (pin "1") (pinfunction "1_1") (pintype "passive"))
      (node (ref "RS_TRANS_9") (pin "Y") (pinfunction "Y_Y") (pintype "bidirectional"))
      (node (ref "U$4") (pin "19") (pinfunction "19_19") (pintype "bidirectional"))
    )
    (net (code "58") (name "JACK_13_TX-") (class "Default")
      (node (ref "R20") (pin "2") (pinfunction "2_2") (pintype "passive"))
      (node (ref "RS_TRANS_9") (pin "Z") (pinfunction "Z_Z") (pintype "bidirectional"))
      (node (ref "U$4") (pin "20") (pinfunction "20_20") (pintype "bidirectional"))
    )
    (net (code "59") (name "JACK_14_RX+") (class "Default")
      (node (ref "R14") (pin "2") (pinfunction "2_2") (pintype "passive"))
      (node (ref "RS_TRANS_7") (pin "A") (pinfunction "A_A") (pintype "bidirectional"))
      (node (ref "U$4") (pin "13") (pinfunction "13_13") (pintype "bidirectional"))
    )
    (net (code "60") (name "JACK_14_RX-") (class "Default")
      (node (ref "R14") (pin "1") (pinfunction "1_1") (pintype "passive"))
      (node (ref "RS_TRANS_7") (pin "B") (pinfunction "B_B") (pintype "bidirectional"))
      (node (ref "U$4") (pin "14") (pinfunction "14_14") (pintype "bidirectional"))
    )
    (net (code "61") (name "JACK_14_TX+") (class "Default")
      (node (ref "R16") (pin "1") (pinfunction "1_1") (pintype "passive"))
      (node (ref "RS_TRANS_7") (pin "Y") (pinfunction "Y_Y") (pintype "bidirectional"))
      (node (ref "U$4") (pin "15") (pinfunction "15_15") (pintype "bidirectional"))
    )
    (net (code "62") (name "JACK_14_TX-") (class "Default")
      (node (ref "R16") (pin "2") (pinfunction "2_2") (pintype "passive"))
      (node (ref "RS_TRANS_7") (pin "Z") (pinfunction "Z_Z") (pintype "bidirectional"))
      (node (ref "U$4") (pin "16") (pinfunction "16_16") (pintype "bidirectional"))
    )
    (net (code "63") (name "JACK_15_RX+") (class "Default")
      (node (ref "R10") (pin "2") (pinfunction "2_2") (pintype "passive"))
      (node (ref "RS_TRANS_5") (pin "A") (pinfunction "A_A") (pintype "bidirectional"))
      (node (ref "U$4") (pin "9") (pinfunction "9_9") (pintype "bidirectional"))
    )
    (net (code "64") (name "JACK_15_RX-") (class "Default")
      (node (ref "R10") (pin "1") (pinfunction "1_1") (pintype "passive"))
      (node (ref "RS_TRANS_5") (pin "B") (pinfunction "B_B") (pintype "bidirectional"))
      (node (ref "U$4") (pin "10") (pinfunction "10_10") (pintype "bidirectional"))
    )
    (net (code "65") (name "JACK_15_TX+") (class "Default")
      (node (ref "R12") (pin "1") (pinfunction "1_1") (pintype "passive"))
      (node (ref "RS_TRANS_5") (pin "Y") (pinfunction "Y_Y") (pintype "bidirectional"))
      (node (ref "U$4") (pin "11") (pinfunction "11_11") (pintype "bidirectional"))
    )
    (net (code "66") (name "JACK_15_TX-") (class "Default")
      (node (ref "R12") (pin "2") (pinfunction "2_2") (pintype "passive"))
      (node (ref "RS_TRANS_5") (pin "Z") (pinfunction "Z_Z") (pintype "bidirectional"))
      (node (ref "U$4") (pin "12") (pinfunction "12_12") (pintype "bidirectional"))
    )
    (net (code "67") (name "JACK_16_RX+") (class "Default")
      (node (ref "R6") (pin "2") (pinfunction "2_2") (pintype "passive"))
      (node (ref "RS_TRANS_3") (pin "A") (pinfunction "A_A") (pintype "bidirectional"))
      (node (ref "U$4") (pin "5") (pinfunction "5_5") (pintype "bidirectional"))
    )
    (net (code "68") (name "JACK_16_RX-") (class "Default")
      (node (ref "R6") (pin "1") (pinfunction "1_1") (pintype "passive"))
      (node (ref "RS_TRANS_3") (pin "B") (pinfunction "B_B") (pintype "bidirectional"))
      (node (ref "U$4") (pin "6") (pinfunction "6_6") (pintype "bidirectional"))
    )
    (net (code "69") (name "JACK_16_TX+") (class "Default")
      (node (ref "R8") (pin "1") (pinfunction "1_1") (pintype "passive"))
      (node (ref "RS_TRANS_3") (pin "Y") (pinfunction "Y_Y") (pintype "bidirectional"))
      (node (ref "U$4") (pin "7") (pinfunction "7_7") (pintype "bidirectional"))
    )
    (net (code "70") (name "JACK_16_TX-") (class "Default")
      (node (ref "R8") (pin "2") (pinfunction "2_2") (pintype "passive"))
      (node (ref "RS_TRANS_3") (pin "Z") (pinfunction "Z_Z") (pintype "bidirectional"))
      (node (ref "U$4") (pin "8") (pinfunction "8_8") (pintype "bidirectional"))
    )
    (net (code "71") (name "JACK_17_RX+") (class "Default")
      (node (ref "R2") (pin "2") (pinfunction "2_2") (pintype "passive"))
      (node (ref "RS_TRANS_1") (pin "A") (pinfunction "A_A") (pintype "bidirectional"))
      (node (ref "U$4") (pin "1") (pinfunction "1_1") (pintype "bidirectional"))
    )
    (net (code "72") (name "JACK_17_RX-") (class "Default")
      (node (ref "R2") (pin "1") (pinfunction "1_1") (pintype "passive"))
      (node (ref "RS_TRANS_1") (pin "B") (pinfunction "B_B") (pintype "bidirectional"))
      (node (ref "U$4") (pin "2") (pinfunction "2_2") (pintype "bidirectional"))
    )
    (net (code "73") (name "JACK_17_TX+") (class "Default")
      (node (ref "R4") (pin "1") (pinfunction "1_1") (pintype "passive"))
      (node (ref "RS_TRANS_1") (pin "Y") (pinfunction "Y_Y") (pintype "bidirectional"))
      (node (ref "U$4") (pin "3") (pinfunction "3_3") (pintype "bidirectional"))
    )
    (net (code "74") (name "JACK_17_TX-") (class "Default")
      (node (ref "R4") (pin "2") (pinfunction "2_2") (pintype "passive"))
      (node (ref "RS_TRANS_1") (pin "Z") (pinfunction "Z_Z") (pintype "bidirectional"))
      (node (ref "U$4") (pin "4") (pinfunction "4_4") (pintype "bidirectional"))
    )
    (net (code "75") (name "Net-(D1-PadA)") (class "Default")
      (node (ref "D1") (pin "A") (pinfunction "A_A") (pintype "passive"))
      (node (ref "R1") (pin "2") (pinfunction "2_2") (pintype "passive"))
    )
    (net (code "76") (name "Net-(R27-Pad1)") (class "Default")
      (node (ref "R27") (pin "1") (pinfunction "1_1") (pintype "passive"))
      (node (ref "RS-485-2") (pin "B") (pinfunction "B_B") (pintype "bidirectional"))
      (node (ref "U$2") (pin "2") (pinfunction "2_2") (pintype "bidirectional"))
    )
    (net (code "77") (name "Net-(R27-Pad2)") (class "Default")
      (node (ref "R27") (pin "2") (pinfunction "2_2") (pintype "passive"))
      (node (ref "RS-485-2") (pin "A") (pinfunction "A_A") (pintype "bidirectional"))
      (node (ref "U$2") (pin "1") (pinfunction "1_1") (pintype "bidirectional"))
    )
    (net (code "78") (name "Net-(R29-Pad1)") (class "Default")
      (node (ref "R29") (pin "1") (pinfunction "1_1") (pintype "passive"))
      (node (ref "RS-485-2") (pin "Y") (pinfunction "Y_Y") (pintype "bidirectional"))
      (node (ref "U$2") (pin "3") (pinfunction "3_3") (pintype "bidirectional"))
    )
    (net (code "79") (name "Net-(R29-Pad2)") (class "Default")
      (node (ref "R29") (pin "2") (pinfunction "2_2") (pintype "passive"))
      (node (ref "RS-485-2") (pin "Z") (pinfunction "Z_Z") (pintype "bidirectional"))
      (node (ref "U$2") (pin "6") (pinfunction "6_6") (pintype "bidirectional"))
    )
    (net (code "80") (name "Net-(R38-Pad1)") (class "Default")
      (node (ref "R38") (pin "1") (pinfunction "1_1") (pintype "passive"))
      (node (ref "RS-485-1") (pin "B") (pinfunction "B_B") (pintype "bidirectional"))
      (node (ref "U$1") (pin "2") (pinfunction "2_2") (pintype "bidirectional"))
    )
    (net (code "81") (name "Net-(R38-Pad2)") (class "Default")
      (node (ref "R38") (pin "2") (pinfunction "2_2") (pintype "passive"))
      (node (ref "RS-485-1") (pin "A") (pinfunction "A_A") (pintype "bidirectional"))
      (node (ref "U$1") (pin "1") (pinfunction "1_1") (pintype "bidirectional"))
    )
    (net (code "82") (name "Net-(R39-Pad1)") (class "Default")
      (node (ref "R39") (pin "1") (pinfunction "1_1") (pintype "passive"))
      (node (ref "RS-485-1") (pin "Y") (pinfunction "Y_Y") (pintype "bidirectional"))
      (node (ref "U$1") (pin "3") (pinfunction "3_3") (pintype "bidirectional"))
    )
    (net (code "83") (name "Net-(R39-Pad2)") (class "Default")
      (node (ref "R39") (pin "2") (pinfunction "2_2") (pintype "passive"))
      (node (ref "RS-485-1") (pin "Z") (pinfunction "Z_Z") (pintype "bidirectional"))
      (node (ref "U$1") (pin "6") (pinfunction "6_6") (pintype "bidirectional"))
    )
    (net (code "84") (name "OUT_1") (class "Default")
      (node (ref "U$3") (pin "1") (pinfunction "S1_1") (pintype "bidirectional"))
      (node (ref "U$7") (pin "R") (pinfunction "R_R") (pintype "bidirectional"))
    )
    (net (code "85") (name "OUT_2") (class "Default")
      (node (ref "U$3") (pin "3") (pinfunction "S2_3") (pintype "bidirectional"))
      (node (ref "U$6") (pin "R") (pinfunction "R_R") (pintype "bidirectional"))
    )
    (net (code "86") (name "U2_SENSOR_RX") (class "Default")
      (node (ref "RS-485-1") (pin "RO") (pinfunction "R0_RO") (pintype "bidirectional"))
      (node (ref "U$5") (pin "P33") (pinfunction "PA6_P33") (pintype "bidirectional"))
    )
    (net (code "87") (name "U2_SENSOR_TX") (class "Default")
      (node (ref "RS-485-1") (pin "DI") (pinfunction "DI_DI") (pintype "bidirectional"))
      (node (ref "U$5") (pin "P57") (pinfunction "PA7_P57") (pintype "bidirectional"))
    )
    (net (code "88") (name "U3RX") (class "Default")
      (node (ref "U$5") (pin "P12") (pinfunction "PA4_P12") (pintype "bidirectional"))
      (node (ref "U3_MUX") (pin "13") (pinfunction "1Z_13") (pintype "bidirectional"))
    )
    (net (code "89") (name "U3TX") (class "Default")
      (node (ref "U$5") (pin "P11") (pinfunction "PA5_P11") (pintype "bidirectional"))
      (node (ref "U3_MUX") (pin "3") (pinfunction "2Z_3") (pintype "bidirectional"))
    )
    (net (code "90") (name "U3_JACK_1_RX") (class "Default")
      (node (ref "RS_TRANS_15") (pin "RO") (pinfunction "R0_RO") (pintype "bidirectional"))
      (node (ref "U3_MUX") (pin "14") (pinfunction "1Y1_14") (pintype "bidirectional"))
    )
    (net (code "91") (name "U3_JACK_1_TX") (class "Default")
      (node (ref "RS_TRANS_15") (pin "DI") (pinfunction "DI_DI") (pintype "bidirectional"))
      (node (ref "U3_MUX") (pin "5") (pinfunction "2Y1_5") (pintype "bidirectional"))
    )
    (net (code "92") (name "U3_JACK_2_RX") (class "Default")
      (node (ref "RS_TRANS_16") (pin "RO") (pinfunction "R0_RO") (pintype "bidirectional"))
      (node (ref "U3_MUX") (pin "15") (pinfunction "1Y2_15") (pintype "bidirectional"))
    )
    (net (code "93") (name "U3_JACK_2_TX") (class "Default")
      (node (ref "RS_TRANS_16") (pin "DI") (pinfunction "DI_DI") (pintype "bidirectional"))
      (node (ref "U3_MUX") (pin "2") (pinfunction "2Y2_2") (pintype "bidirectional"))
    )
    (net (code "94") (name "U3_JACK_3_RX") (class "Default")
      (node (ref "RS_TRANS_17") (pin "RO") (pinfunction "R0_RO") (pintype "bidirectional"))
      (node (ref "U3_MUX") (pin "11") (pinfunction "1Y3_11") (pintype "bidirectional"))
    )
    (net (code "95") (name "U3_JACK_3_TX") (class "Default")
      (node (ref "RS_TRANS_17") (pin "DI") (pinfunction "DI_DI") (pintype "bidirectional"))
      (node (ref "U3_MUX") (pin "4") (pinfunction "2Y3_4") (pintype "bidirectional"))
    )
    (net (code "96") (name "U3_MUX_S0") (class "Default")
      (node (ref "U$5") (pin "P44") (pinfunction "PH0_P44") (pintype "bidirectional"))
      (node (ref "U3_MUX") (pin "10") (pinfunction "S0_10") (pintype "input"))
    )
    (net (code "97") (name "U3_MUX_S1") (class "Default")
      (node (ref "U$5") (pin "P43") (pinfunction "PH1_P43") (pintype "bidirectional"))
      (node (ref "U3_MUX") (pin "9") (pinfunction "S1_9") (pintype "input"))
    )
    (net (code "98") (name "U4RX") (class "Default")
      (node (ref "U$5") (pin "P16") (pinfunction "PK0_P16") (pintype "bidirectional"))
      (node (ref "U4_MUX") (pin "13") (pinfunction "1Z_13") (pintype "bidirectional"))
    )
    (net (code "99") (name "U4TX") (class "Default")
      (node (ref "U$5") (pin "P15") (pinfunction "PK1_P15") (pintype "bidirectional"))
      (node (ref "U4_MUX") (pin "3") (pinfunction "2Z_3") (pintype "bidirectional"))
    )
    (net (code "100") (name "U4_JACK_12_RX") (class "Default")
      (node (ref "RS_TRANS_13") (pin "RO") (pinfunction "R0_RO") (pintype "bidirectional"))
      (node (ref "U4_MUX") (pin "14") (pinfunction "1Y1_14") (pintype "bidirectional"))
    )
    (net (code "101") (name "U4_JACK_12_TX") (class "Default")
      (node (ref "RS_TRANS_13") (pin "DI") (pinfunction "DI_DI") (pintype "bidirectional"))
      (node (ref "U4_MUX") (pin "5") (pinfunction "2Y1_5") (pintype "bidirectional"))
    )
    (net (code "102") (name "U4_JACK_13_RX") (class "Default")
      (node (ref "RS_TRANS_14") (pin "RO") (pinfunction "R0_RO") (pintype "bidirectional"))
      (node (ref "U4_MUX") (pin "15") (pinfunction "1Y2_15") (pintype "bidirectional"))
    )
    (net (code "103") (name "U4_JACK_13_TX") (class "Default")
      (node (ref "RS_TRANS_14") (pin "DI") (pinfunction "DI_DI") (pintype "bidirectional"))
      (node (ref "U4_MUX") (pin "2") (pinfunction "2Y2_2") (pintype "bidirectional"))
    )
    (net (code "104") (name "U4_MUX_S0") (class "Default")
      (node (ref "U$5") (pin "P51") (pinfunction "PM6_P51") (pintype "bidirectional"))
      (node (ref "U4_MUX") (pin "10") (pinfunction "S0_10") (pintype "input"))
    )
    (net (code "105") (name "U4_MUX_S1") (class "Default")
      (node (ref "U$5") (pin "P59") (pinfunction "PM7_P59") (pintype "bidirectional"))
      (node (ref "U4_MUX") (pin "9") (pinfunction "S1_9") (pintype "input"))
    )
    (net (code "106") (name "U4_POWERBOARD_TX") (class "Default")
      (node (ref "RS-485-2") (pin "DI") (pinfunction "DI_DI") (pintype "bidirectional"))
      (node (ref "U4_MUX") (pin "4") (pinfunction "2Y3_4") (pintype "bidirectional"))
    )
    (net (code "107") (name "U4_POWRBOARD_RX") (class "Default")
      (node (ref "RS-485-2") (pin "RO") (pinfunction "R0_RO") (pintype "bidirectional"))
      (node (ref "U4_MUX") (pin "11") (pinfunction "1Y3_11") (pintype "bidirectional"))
    )
    (net (code "108") (name "U5RX") (class "Default")
      (node (ref "U$5") (pin "P26") (pinfunction "PC6_P26") (pintype "bidirectional"))
      (node (ref "U5_MUX") (pin "13") (pinfunction "1Z_13") (pintype "bidirectional"))
    )
    (net (code "109") (name "U5TX") (class "Default")
      (node (ref "U$5") (pin "P23") (pinfunction "PC7_P23") (pintype "bidirectional"))
      (node (ref "U5_MUX") (pin "3") (pinfunction "2Z_3") (pintype "bidirectional"))
    )
    (net (code "110") (name "U5_JACK_4_RX") (class "Default")
      (node (ref "RS_TRANS_7") (pin "RO") (pinfunction "R0_RO") (pintype "bidirectional"))
      (node (ref "U5_MUX") (pin "12") (pinfunction "1Y0_12") (pintype "bidirectional"))
    )
    (net (code "111") (name "U5_JACK_4_TX") (class "Default")
      (node (ref "RS_TRANS_7") (pin "DI") (pinfunction "DI_DI") (pintype "bidirectional"))
      (node (ref "U5_MUX") (pin "1") (pinfunction "2Y0_1") (pintype "bidirectional"))
    )
    (net (code "112") (name "U5_JACK_5_RX") (class "Default")
      (node (ref "RS_TRANS_1") (pin "RO") (pinfunction "R0_RO") (pintype "bidirectional"))
      (node (ref "U5_MUX") (pin "14") (pinfunction "1Y1_14") (pintype "bidirectional"))
    )
    (net (code "113") (name "U5_JACK_5_TX") (class "Default")
      (node (ref "RS_TRANS_1") (pin "DI") (pinfunction "DI_DI") (pintype "bidirectional"))
      (node (ref "U5_MUX") (pin "5") (pinfunction "2Y1_5") (pintype "bidirectional"))
    )
    (net (code "114") (name "U5_JACK_6_RX") (class "Default")
      (node (ref "RS_TRANS_5") (pin "RO") (pinfunction "R0_RO") (pintype "bidirectional"))
      (node (ref "U5_MUX") (pin "15") (pinfunction "1Y2_15") (pintype "bidirectional"))
    )
    (net (code "115") (name "U5_JACK_6_TX") (class "Default")
      (node (ref "RS_TRANS_5") (pin "DI") (pinfunction "DI_DI") (pintype "bidirectional"))
      (node (ref "U5_MUX") (pin "2") (pinfunction "2Y2_2") (pintype "bidirectional"))
    )
    (net (code "116") (name "U5_JACK_7_RX") (class "Default")
      (node (ref "RS_TRANS_3") (pin "RO") (pinfunction "R0_RO") (pintype "bidirectional"))
      (node (ref "U5_MUX") (pin "11") (pinfunction "1Y3_11") (pintype "bidirectional"))
    )
    (net (code "117") (name "U5_JACK_7_TX") (class "Default")
      (node (ref "RS_TRANS_3") (pin "DI") (pinfunction "DI_DI") (pintype "bidirectional"))
      (node (ref "U5_MUX") (pin "4") (pinfunction "2Y3_4") (pintype "bidirectional"))
    )
    (net (code "118") (name "U5_MUX_S0") (class "Default")
      (node (ref "U$5") (pin "P64") (pinfunction "PL0_P64") (pintype "bidirectional"))
      (node (ref "U5_MUX") (pin "10") (pinfunction "S0_10") (pintype "input"))
    )
    (net (code "119") (name "U5_MUX_S1") (class "Default")
      (node (ref "U$5") (pin "P63") (pinfunction "PL1_P63") (pintype "bidirectional"))
      (node (ref "U5_MUX") (pin "9") (pinfunction "S1_9") (pintype "input"))
    )
    (net (code "120") (name "U6RX") (class "Default")
      (node (ref "U$5") (pin "P8") (pinfunction "PP0_P8") (pintype "bidirectional"))
      (node (ref "U6_MUX") (pin "13") (pinfunction "1Z_13") (pintype "bidirectional"))
    )
    (net (code "121") (name "U6TX") (class "Default")
      (node (ref "U$5") (pin "P7") (pinfunction "PP1_P7") (pintype "bidirectional"))
      (node (ref "U6_MUX") (pin "3") (pinfunction "2Z_3") (pintype "bidirectional"))
    )
    (net (code "122") (name "U6_JACK_14_RX") (class "Default")
      (node (ref "RS_TRANS_6") (pin "RO") (pinfunction "R0_RO") (pintype "bidirectional"))
      (node (ref "U6_MUX") (pin "12") (pinfunction "1Y0_12") (pintype "bidirectional"))
    )
    (net (code "123") (name "U6_JACK_14_TX") (class "Default")
      (node (ref "RS_TRANS_6") (pin "DI") (pinfunction "DI_DI") (pintype "bidirectional"))
      (node (ref "U6_MUX") (pin "1") (pinfunction "2Y0_1") (pintype "bidirectional"))
    )
    (net (code "124") (name "U6_JACK_15_RX") (class "Default")
      (node (ref "RS_TRANS_8") (pin "RO") (pinfunction "R0_RO") (pintype "bidirectional"))
      (node (ref "U6_MUX") (pin "14") (pinfunction "1Y1_14") (pintype "bidirectional"))
    )
    (net (code "125") (name "U6_JACK_15_TX") (class "Default")
      (node (ref "RS_TRANS_8") (pin "DI") (pinfunction "DI_DI") (pintype "bidirectional"))
      (node (ref "U6_MUX") (pin "5") (pinfunction "2Y1_5") (pintype "bidirectional"))
    )
    (net (code "126") (name "U6_JACK_16_RX") (class "Default")
      (node (ref "RS_TRANS_10") (pin "RO") (pinfunction "R0_RO") (pintype "bidirectional"))
      (node (ref "U6_MUX") (pin "15") (pinfunction "1Y2_15") (pintype "bidirectional"))
    )
    (net (code "127") (name "U6_JACK_16_TX") (class "Default")
      (node (ref "RS_TRANS_10") (pin "DI") (pinfunction "DI_DI") (pintype "bidirectional"))
      (node (ref "U6_MUX") (pin "2") (pinfunction "2Y2_2") (pintype "bidirectional"))
    )
    (net (code "128") (name "U6_JACK_17_RX") (class "Default")
      (node (ref "RS_TRANS_12") (pin "RO") (pinfunction "R0_RO") (pintype "bidirectional"))
      (node (ref "U6_MUX") (pin "11") (pinfunction "1Y3_11") (pintype "bidirectional"))
    )
    (net (code "129") (name "U6_JACK_17_TX") (class "Default")
      (node (ref "RS_TRANS_12") (pin "DI") (pinfunction "DI_DI") (pintype "bidirectional"))
      (node (ref "U6_MUX") (pin "4") (pinfunction "2Y3_4") (pintype "bidirectional"))
    )
    (net (code "130") (name "U6_MUX_S0") (class "Default")
      (node (ref "U$5") (pin "P14") (pinfunction "PK2_P14") (pintype "bidirectional"))
      (node (ref "U6_MUX") (pin "10") (pinfunction "S0_10") (pintype "input"))
    )
    (net (code "131") (name "U6_MUX_S1") (class "Default")
      (node (ref "U$5") (pin "P13") (pinfunction "PK3_P13") (pintype "bidirectional"))
      (node (ref "U6_MUX") (pin "9") (pinfunction "S1_9") (pintype "input"))
    )
    (net (code "132") (name "U7RX") (class "Default")
      (node (ref "U$5") (pin "P28") (pinfunction "PC4_P28") (pintype "bidirectional"))
      (node (ref "U7_MUX") (pin "13") (pinfunction "1Z_13") (pintype "bidirectional"))
    )
    (net (code "133") (name "U7TX") (class "Default")
      (node (ref "U$5") (pin "P27") (pinfunction "PC5_P27") (pintype "bidirectional"))
      (node (ref "U7_MUX") (pin "3") (pinfunction "2Z_3") (pintype "bidirectional"))
    )
    (net (code "134") (name "U7_JACK_8_RX") (class "Default")
      (node (ref "RS_TRANS_11") (pin "RO") (pinfunction "R0_RO") (pintype "bidirectional"))
      (node (ref "U7_MUX") (pin "12") (pinfunction "1Y0_12") (pintype "bidirectional"))
    )
    (net (code "135") (name "U7_JACK_8_TX") (class "Default")
      (node (ref "RS_TRANS_11") (pin "DI") (pinfunction "DI_DI") (pintype "bidirectional"))
      (node (ref "U7_MUX") (pin "1") (pinfunction "2Y0_1") (pintype "bidirectional"))
    )
    (net (code "136") (name "U7_JACK_9_RX") (class "Default")
      (node (ref "RS_TRANS_2") (pin "RO") (pinfunction "R0_RO") (pintype "bidirectional"))
      (node (ref "U7_MUX") (pin "14") (pinfunction "1Y1_14") (pintype "bidirectional"))
    )
    (net (code "137") (name "U7_JACK_9_TX") (class "Default")
      (node (ref "RS_TRANS_2") (pin "DI") (pinfunction "DI_DI") (pintype "bidirectional"))
      (node (ref "U7_MUX") (pin "5") (pinfunction "2Y1_5") (pintype "bidirectional"))
    )
    (net (code "138") (name "U7_JACK_10_RX") (class "Default")
      (node (ref "RS_TRANS_4") (pin "RO") (pinfunction "R0_RO") (pintype "bidirectional"))
      (node (ref "U7_MUX") (pin "15") (pinfunction "1Y2_15") (pintype "bidirectional"))
    )
    (net (code "139") (name "U7_JACK_10_TX") (class "Default")
      (node (ref "RS_TRANS_4") (pin "DI") (pinfunction "DI_DI") (pintype "bidirectional"))
      (node (ref "U7_MUX") (pin "2") (pinfunction "2Y2_2") (pintype "bidirectional"))
    )
    (net (code "140") (name "U7_JACK_11_RX") (class "Default")
      (node (ref "RS_TRANS_9") (pin "RO") (pinfunction "R0_RO") (pintype "bidirectional"))
      (node (ref "U7_MUX") (pin "11") (pinfunction "1Y3_11") (pintype "bidirectional"))
    )
    (net (code "141") (name "U7_JACK_11_TX") (class "Default")
      (node (ref "RS_TRANS_9") (pin "DI") (pinfunction "DI_DI") (pintype "bidirectional"))
      (node (ref "U7_MUX") (pin "4") (pinfunction "2Y3_4") (pintype "bidirectional"))
    )
    (net (code "142") (name "U7_MUX_S0") (class "Default")
      (node (ref "U$5") (pin "P38") (pinfunction "PE0_P38") (pintype "bidirectional"))
      (node (ref "U7_MUX") (pin "10") (pinfunction "S0_10") (pintype "input"))
    )
    (net (code "143") (name "U7_MUX_S1") (class "Default")
      (node (ref "U$5") (pin "P37") (pinfunction "PE1_P37") (pintype "bidirectional"))
      (node (ref "U7_MUX") (pin "9") (pinfunction "S1_9") (pintype "input"))
    )
    (net (code "144") (name "unconnected-(U$2-Pad4)") (class "Default")
      (node (ref "U$2") (pin "4") (pinfunction "4_4") (pintype "bidirectional"))
    )
    (net (code "145") (name "unconnected-(U$2-Pad5)") (class "Default")
      (node (ref "U$2") (pin "5") (pinfunction "5_5") (pintype "bidirectional"))
    )
    (net (code "146") (name "unconnected-(U$2-Pad7)") (class "Default")
      (node (ref "U$2") (pin "7") (pinfunction "7_7") (pintype "bidirectional"))
    )
    (net (code "147") (name "unconnected-(U$2-Pad8)") (class "Default")
      (node (ref "U$2") (pin "8") (pinfunction "8_8") (pintype "bidirectional"))
    )
    (net (code "148") (name "unconnected-(U$5-5V_1-PadP40)") (class "Default")
      (node (ref "U$5") (pin "P40") (pinfunction "5V_1_P40") (pintype "bidirectional"))
    )
    (net (code "149") (name "unconnected-(U$5-5V_2-PadP20)") (class "Default")
      (node (ref "U$5") (pin "P20") (pinfunction "5V_2_P20") (pintype "bidirectional"))
    )
    (net (code "150") (name "unconnected-(U$5-PA2{slash}PQ3-PadP54)") (class "Default")
      (node (ref "U$5") (pin "P54") (pinfunction "PA2/PQ3_P54") (pintype "bidirectional"))
    )
    (net (code "151") (name "unconnected-(U$5-PA3{slash}PQ2-PadP55)") (class "Default")
      (node (ref "U$5") (pin "P55") (pinfunction "PA3/PQ2_P55") (pintype "bidirectional"))
    )
    (net (code "152") (name "unconnected-(U$5-PB2-PadP22)") (class "Default")
      (node (ref "U$5") (pin "P22") (pinfunction "PB2_P22") (pintype "bidirectional"))
    )
    (net (code "153") (name "unconnected-(U$5-PB3-PadP21)") (class "Default")
      (node (ref "U$5") (pin "P21") (pinfunction "PB3_P21") (pintype "bidirectional"))
    )
    (net (code "154") (name "unconnected-(U$5-PB4-PadP18)") (class "Default")
      (node (ref "U$5") (pin "P18") (pinfunction "PB4_P18") (pintype "bidirectional"))
    )
    (net (code "155") (name "unconnected-(U$5-PB5-PadP17)") (class "Default")
      (node (ref "U$5") (pin "P17") (pinfunction "PB5_P17") (pintype "bidirectional"))
    )
    (net (code "156") (name "unconnected-(U$5-PD0-PadP74)") (class "Default")
      (node (ref "U$5") (pin "P74") (pinfunction "PD0_P74") (pintype "bidirectional"))
    )
    (net (code "157") (name "unconnected-(U$5-PD1-PadP75)") (class "Default")
      (node (ref "U$5") (pin "P75") (pinfunction "PD1_P75") (pintype "bidirectional"))
    )
    (net (code "158") (name "unconnected-(U$5-PD2-PadP9)") (class "Default")
      (node (ref "U$5") (pin "P9") (pinfunction "PD2_P9") (pintype "bidirectional"))
    )
    (net (code "159") (name "unconnected-(U$5-PD3-PadP24)") (class "Default")
      (node (ref "U$5") (pin "P24") (pinfunction "PD3_P24") (pintype "bidirectional"))
    )
    (net (code "160") (name "unconnected-(U$5-PD7-PadP34)") (class "Default")
      (node (ref "U$5") (pin "P34") (pinfunction "PD7_P34") (pintype "bidirectional"))
    )
    (net (code "161") (name "unconnected-(U$5-PE2-PadP36)") (class "Default")
      (node (ref "U$5") (pin "P36") (pinfunction "PE2_P36") (pintype "bidirectional"))
    )
    (net (code "162") (name "unconnected-(U$5-PE3-PadP35)") (class "Default")
      (node (ref "U$5") (pin "P35") (pinfunction "PE3_P35") (pintype "bidirectional"))
    )
    (net (code "163") (name "unconnected-(U$5-PE4-PadP29)") (class "Default")
      (node (ref "U$5") (pin "P29") (pinfunction "PE4_P29") (pintype "bidirectional"))
    )
    (net (code "164") (name "unconnected-(U$5-PE5-PadP25)") (class "Default")
      (node (ref "U$5") (pin "P25") (pinfunction "PE5_P25") (pintype "bidirectional"))
    )
    (net (code "165") (name "unconnected-(U$5-PF1-PadP70)") (class "Default")
      (node (ref "U$5") (pin "P70") (pinfunction "PF1_P70") (pintype "bidirectional"))
    )
    (net (code "166") (name "unconnected-(U$5-PF2-PadP69)") (class "Default")
      (node (ref "U$5") (pin "P69") (pinfunction "PF2_P69") (pintype "bidirectional"))
    )
    (net (code "167") (name "unconnected-(U$5-PF3-PadP68)") (class "Default")
      (node (ref "U$5") (pin "P68") (pinfunction "PF3_P68") (pintype "bidirectional"))
    )
    (net (code "168") (name "unconnected-(U$5-PG0-PadP67)") (class "Default")
      (node (ref "U$5") (pin "P67") (pinfunction "PG0_P67") (pintype "bidirectional"))
    )
    (net (code "169") (name "unconnected-(U$5-PG1-PadP50)") (class "Default")
      (node (ref "U$5") (pin "P50") (pinfunction "PG1_P50") (pintype "bidirectional"))
    )
    (net (code "170") (name "unconnected-(U$5-PH2-PadP78)") (class "Default")
      (node (ref "U$5") (pin "P78") (pinfunction "PH2_P78") (pintype "bidirectional"))
    )
    (net (code "171") (name "unconnected-(U$5-PH3-PadP77)") (class "Default")
      (node (ref "U$5") (pin "P77") (pinfunction "PH3_P77") (pintype "bidirectional"))
    )
    (net (code "172") (name "unconnected-(U$5-PK4-PadP49)") (class "Default")
      (node (ref "U$5") (pin "P49") (pinfunction "PK4_P49") (pintype "bidirectional"))
    )
    (net (code "173") (name "unconnected-(U$5-PK5-PadP48)") (class "Default")
      (node (ref "U$5") (pin "P48") (pinfunction "PK5_P48") (pintype "bidirectional"))
    )
    (net (code "174") (name "unconnected-(U$5-PK6-PadP42)") (class "Default")
      (node (ref "U$5") (pin "P42") (pinfunction "PK6_P42") (pintype "bidirectional"))
    )
    (net (code "175") (name "unconnected-(U$5-PK7-PadP41)") (class "Default")
      (node (ref "U$5") (pin "P41") (pinfunction "PK7_P41") (pintype "bidirectional"))
    )
    (net (code "176") (name "unconnected-(U$5-PL2-PadP62)") (class "Default")
      (node (ref "U$5") (pin "P62") (pinfunction "PL2_P62") (pintype "bidirectional"))
    )
    (net (code "177") (name "unconnected-(U$5-PL3-PadP61)") (class "Default")
      (node (ref "U$5") (pin "P61") (pinfunction "PL3_P61") (pintype "bidirectional"))
    )
    (net (code "178") (name "unconnected-(U$5-PL4-PadP66)") (class "Default")
      (node (ref "U$5") (pin "P66") (pinfunction "PL4_P66") (pintype "bidirectional"))
    )
    (net (code "179") (name "unconnected-(U$5-PM0-PadP47)") (class "Default")
      (node (ref "U$5") (pin "P47") (pinfunction "PM0_P47") (pintype "bidirectional"))
    )
    (net (code "180") (name "unconnected-(U$5-PM1-PadP46)") (class "Default")
      (node (ref "U$5") (pin "P46") (pinfunction "PM1_P46") (pintype "bidirectional"))
    )
    (net (code "181") (name "unconnected-(U$5-PM2-PadP45)") (class "Default")
      (node (ref "U$5") (pin "P45") (pinfunction "PM2_P45") (pintype "bidirectional"))
    )
    (net (code "182") (name "unconnected-(U$5-PM3-PadP79)") (class "Default")
      (node (ref "U$5") (pin "P79") (pinfunction "PM3_P79") (pintype "bidirectional"))
    )
    (net (code "183") (name "unconnected-(U$5-PM4-PadP32)") (class "Default")
      (node (ref "U$5") (pin "P32") (pinfunction "PM4_P32") (pintype "bidirectional"))
    )
    (net (code "184") (name "unconnected-(U$5-PM5-PadP31)") (class "Default")
      (node (ref "U$5") (pin "P31") (pinfunction "PM5_P31") (pintype "bidirectional"))
    )
    (net (code "185") (name "unconnected-(U$5-PN2-PadP73)") (class "Default")
      (node (ref "U$5") (pin "P73") (pinfunction "PN2_P73") (pintype "bidirectional"))
    )
    (net (code "186") (name "unconnected-(U$5-PN3-PadP72)") (class "Default")
      (node (ref "U$5") (pin "P72") (pinfunction "PN3_P72") (pintype "bidirectional"))
    )
    (net (code "187") (name "unconnected-(U$5-PN4-PadP1)") (class "Default")
      (node (ref "U$5") (pin "P1") (pinfunction "PN4_P1") (pintype "bidirectional"))
    )
    (net (code "188") (name "unconnected-(U$5-PN5-PadP2)") (class "Default")
      (node (ref "U$5") (pin "P2") (pinfunction "PN5_P2") (pintype "bidirectional"))
    )
    (net (code "189") (name "unconnected-(U$5-PP2-PadP71)") (class "Default")
      (node (ref "U$5") (pin "P71") (pinfunction "PP2_P71") (pintype "bidirectional"))
    )
    (net (code "190") (name "unconnected-(U$5-PP3-PadP53)") (class "Default")
      (node (ref "U$5") (pin "P53") (pinfunction "PP3_P53") (pintype "bidirectional"))
    )
    (net (code "191") (name "unconnected-(U$5-PP4-PadP3)") (class "Default")
      (node (ref "U$5") (pin "P3") (pinfunction "PP4_P3") (pintype "bidirectional"))
    )
    (net (code "192") (name "unconnected-(U$5-PP5-PadP58)") (class "Default")
      (node (ref "U$5") (pin "P58") (pinfunction "PP5_P58") (pintype "bidirectional"))
    )
    (net (code "193") (name "unconnected-(U$5-PQ0-PadP4)") (class "Default")
      (node (ref "U$5") (pin "P4") (pinfunction "PQ0_P4") (pintype "bidirectional"))
    )
    (net (code "194") (name "unconnected-(U$5-PQ1-PadP52)") (class "Default")
      (node (ref "U$5") (pin "P52") (pinfunction "PQ1_P52") (pintype "bidirectional"))
    )
    (net (code "195") (name "unconnected-(U$5-RST_1-PadP76)") (class "Default")
      (node (ref "U$5") (pin "P76") (pinfunction "RST_1_P76") (pintype "bidirectional"))
    )
    (net (code "196") (name "unconnected-(U$5-RST_2-PadP56)") (class "Default")
      (node (ref "U$5") (pin "P56") (pinfunction "RST_2_P56") (pintype "bidirectional"))
    )
    (net (code "197") (name "unconnected-(U3_MUX-1Y0-Pad12)") (class "Default")
      (node (ref "U3_MUX") (pin "12") (pinfunction "1Y0_12") (pintype "bidirectional"))
    )
    (net (code "198") (name "unconnected-(U3_MUX-2Y0-Pad1)") (class "Default")
      (node (ref "U3_MUX") (pin "1") (pinfunction "2Y0_1") (pintype "bidirectional"))
    )
    (net (code "199") (name "unconnected-(U4_MUX-1Y0-Pad12)") (class "Default")
      (node (ref "U4_MUX") (pin "12") (pinfunction "1Y0_12") (pintype "bidirectional"))
    )
    (net (code "200") (name "unconnected-(U4_MUX-2Y0-Pad1)") (class "Default")
      (node (ref "U4_MUX") (pin "1") (pinfunction "2Y0_1") (pintype "bidirectional"))
    )
  )
)
